# bontor_mbed_lowpan_rev_e.net
KiCad netlist of a schematic drawn in EAGLE
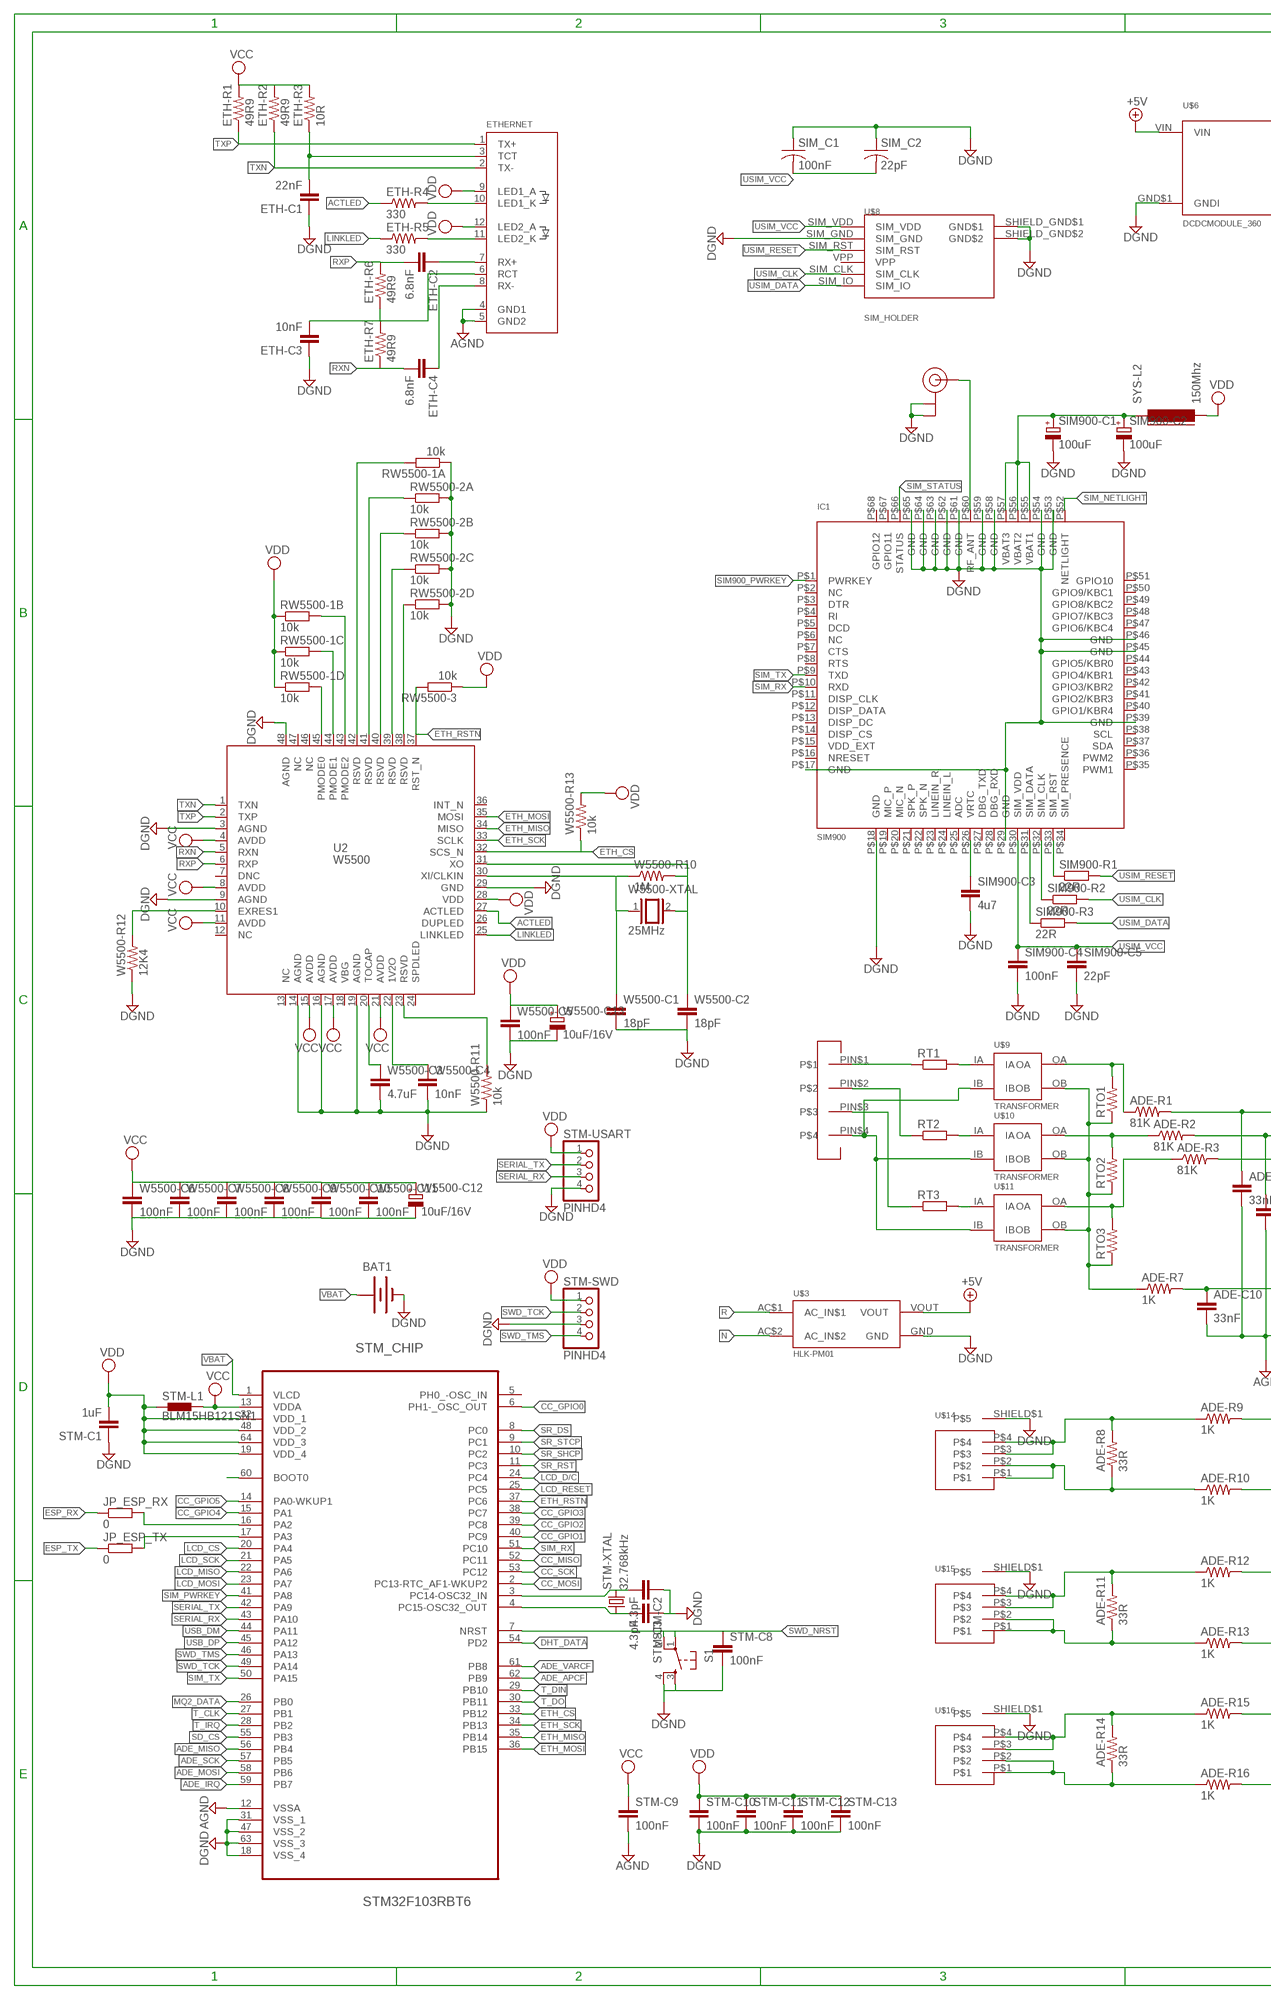
[diagram p0: schematic, sheet 1, part 1 of 2]
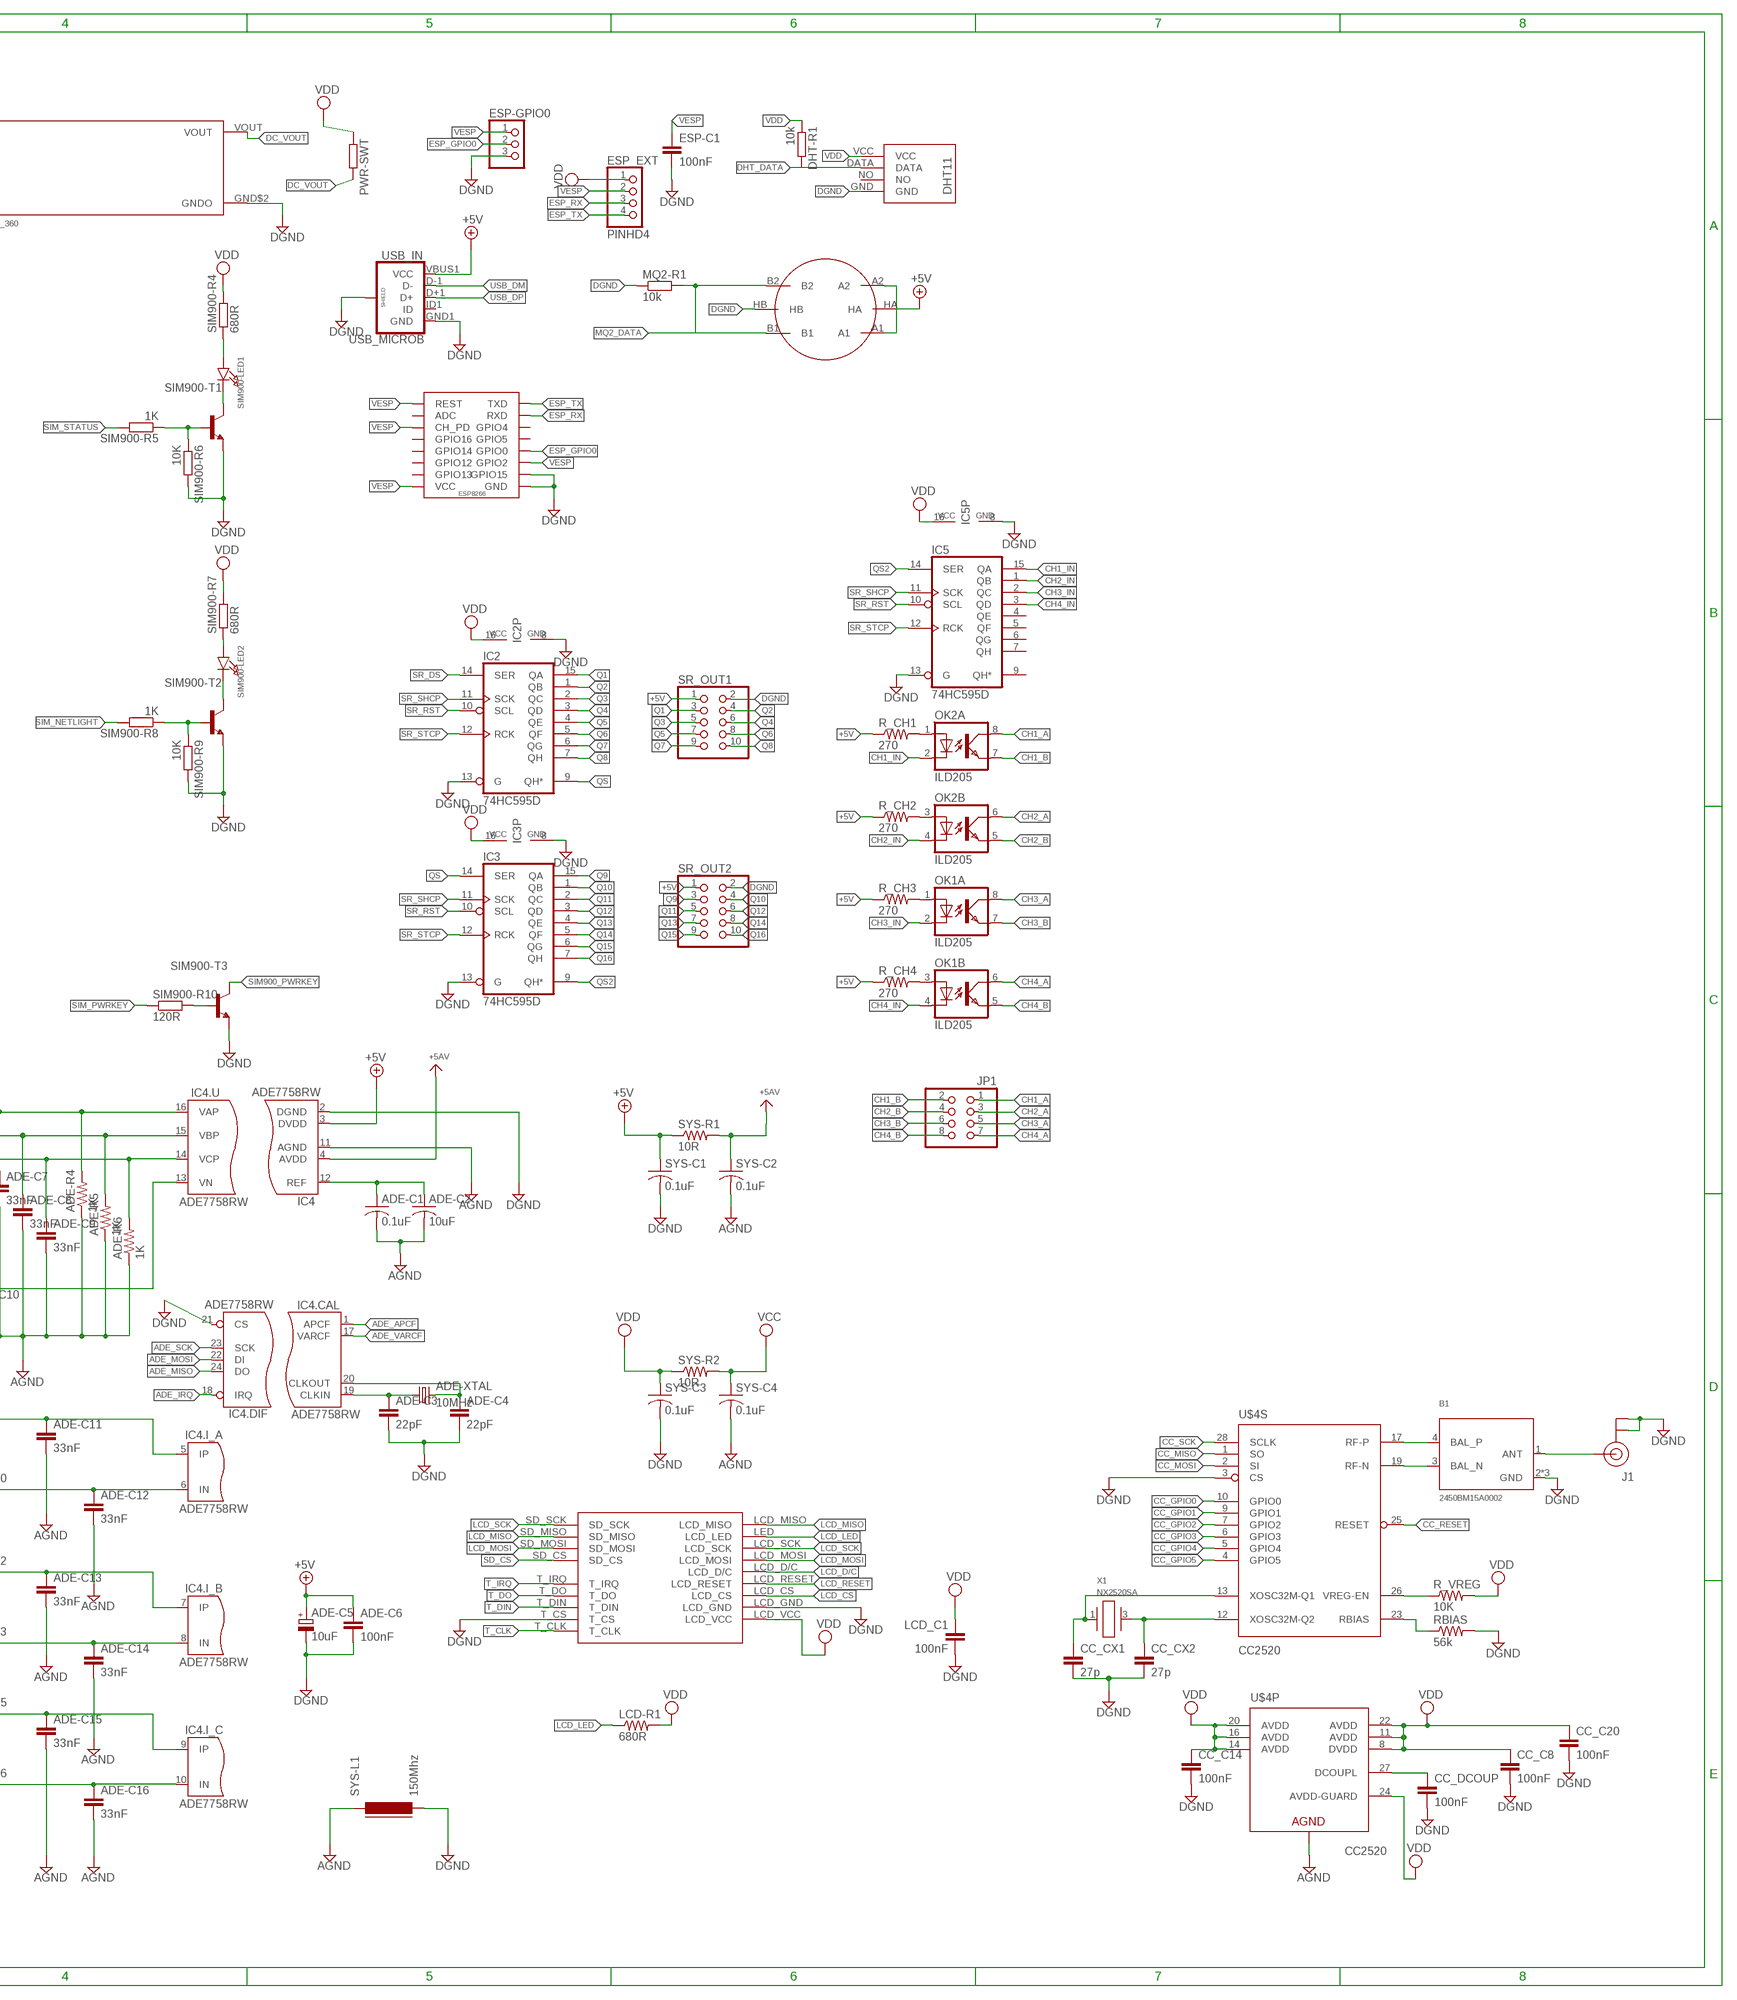
[diagram p1: schematic, sheet 1, part 2 of 2]

(export (version "E")
  (design (tool "Eeschema 10.0.6"))
  (components
    (comp (ref "ADE-C1")
      (value "0.1uF")
      (footprint "eagle-import:C0603@1")
      (libsource (lib "eagle-import") (part "C-USC0603"))
    )
    (comp (ref "ADE-C2")
      (value "10uF")
      (footprint "eagle-import:C0805K")
      (libsource (lib "eagle-import") (part "C-USC0805K"))
    )
    (comp (ref "ADE-C3")
      (value "22pF")
      (footprint "eagle-import:C0603")
      (libsource (lib "eagle-import") (part "C-EUC0603"))
    )
    (comp (ref "ADE-C4")
      (value "22pF")
      (footprint "eagle-import:C0603")
      (libsource (lib "eagle-import") (part "C-EUC0603"))
    )
    (comp (ref "ADE-C5")
      (value "10uF")
      (footprint "eagle-import:153CLV-0605")
      (libsource (lib "eagle-import") (part "CPOL-EU153CLV-0605"))
    )
    (comp (ref "ADE-C6")
      (value "100nF")
      (footprint "eagle-import:C0603")
      (libsource (lib "eagle-import") (part "C-EUC0603"))
    )
    (comp (ref "ADE-C7")
      (value "33nF")
      (footprint "eagle-import:0603-CAP")
      (libsource (lib "eagle-import") (part "CAP0603-CAP"))
    )
    (comp (ref "ADE-C8")
      (value "33nF")
      (footprint "eagle-import:0603-CAP")
      (libsource (lib "eagle-import") (part "CAP0603-CAP"))
    )
    (comp (ref "ADE-C9")
      (value "33nF")
      (footprint "eagle-import:0603-CAP")
      (libsource (lib "eagle-import") (part "CAP0603-CAP"))
    )
    (comp (ref "ADE-C10")
      (value "33nF")
      (footprint "eagle-import:0603-CAP")
      (libsource (lib "eagle-import") (part "CAP0603-CAP"))
    )
    (comp (ref "ADE-C11")
      (value "33nF")
      (footprint "eagle-import:0402-CAP")
      (libsource (lib "eagle-import") (part "CAP0402-CAP"))
    )
    (comp (ref "ADE-C12")
      (value "33nF")
      (footprint "eagle-import:0402-CAP")
      (libsource (lib "eagle-import") (part "CAP0402-CAP"))
    )
    (comp (ref "ADE-C13")
      (value "33nF")
      (footprint "eagle-import:0402-CAP")
      (libsource (lib "eagle-import") (part "CAP0402-CAP"))
    )
    (comp (ref "ADE-C14")
      (value "33nF")
      (footprint "eagle-import:0402-CAP")
      (libsource (lib "eagle-import") (part "CAP0402-CAP"))
    )
    (comp (ref "ADE-C15")
      (value "33nF")
      (footprint "eagle-import:0402-CAP")
      (libsource (lib "eagle-import") (part "CAP0402-CAP"))
    )
    (comp (ref "ADE-C16")
      (value "33nF")
      (footprint "eagle-import:0402-CAP")
      (libsource (lib "eagle-import") (part "CAP0402-CAP"))
    )
    (comp (ref "ADE-R1")
      (value "81K")
      (footprint "eagle-import:0603-RES")
      (libsource (lib "eagle-import") (part "RESISTOR0603-RES"))
    )
    (comp (ref "ADE-R2")
      (value "81K")
      (footprint "eagle-import:0603-RES")
      (libsource (lib "eagle-import") (part "RESISTOR0603-RES"))
    )
    (comp (ref "ADE-R3")
      (value "81K")
      (footprint "eagle-import:0603-RES")
      (libsource (lib "eagle-import") (part "RESISTOR0603-RES"))
    )
    (comp (ref "ADE-R4")
      (value "1K")
      (footprint "eagle-import:0603-RES")
      (libsource (lib "eagle-import") (part "RESISTOR0603-RES"))
    )
    (comp (ref "ADE-R5")
      (value "1K")
      (footprint "eagle-import:0603-RES")
      (libsource (lib "eagle-import") (part "RESISTOR0603-RES"))
    )
    (comp (ref "ADE-R6")
      (value "1K")
      (footprint "eagle-import:0603-RES")
      (libsource (lib "eagle-import") (part "RESISTOR0603-RES"))
    )
    (comp (ref "ADE-R7")
      (value "1K")
      (footprint "eagle-import:0603-RES")
      (libsource (lib "eagle-import") (part "RESISTOR0603-RES"))
    )
    (comp (ref "ADE-R8")
      (value "33R")
      (footprint "eagle-import:0402-RES")
      (libsource (lib "eagle-import") (part "RESISTOR0402-RES"))
    )
    (comp (ref "ADE-R9")
      (value "1K")
      (footprint "eagle-import:0402-RES")
      (libsource (lib "eagle-import") (part "RESISTOR0402-RES"))
    )
    (comp (ref "ADE-R10")
      (value "1K")
      (footprint "eagle-import:0402-RES")
      (libsource (lib "eagle-import") (part "RESISTOR0402-RES"))
    )
    (comp (ref "ADE-R11")
      (value "33R")
      (footprint "eagle-import:0402-RES")
      (libsource (lib "eagle-import") (part "RESISTOR0402-RES"))
    )
    (comp (ref "ADE-R12")
      (value "1K")
      (footprint "eagle-import:0402-RES")
      (libsource (lib "eagle-import") (part "RESISTOR0402-RES"))
    )
    (comp (ref "ADE-R13")
      (value "1K")
      (footprint "eagle-import:0402-RES")
      (libsource (lib "eagle-import") (part "RESISTOR0402-RES"))
    )
    (comp (ref "ADE-R14")
      (value "33R")
      (footprint "eagle-import:0402-RES")
      (libsource (lib "eagle-import") (part "RESISTOR0402-RES"))
    )
    (comp (ref "ADE-R15")
      (value "1K")
      (footprint "eagle-import:0402-RES")
      (libsource (lib "eagle-import") (part "RESISTOR0402-RES"))
    )
    (comp (ref "ADE-R16")
      (value "1K")
      (footprint "eagle-import:0402-RES")
      (libsource (lib "eagle-import") (part "RESISTOR0402-RES"))
    )
    (comp (ref "ADE-XTAL")
      (value "10MHz")
      (footprint "eagle-import:HC49US")
      (libsource (lib "eagle-import") (part "CRYSTALHC49US"))
    )
    (comp (ref "B1")
      (value "2450BM15A0002")
      (footprint "eagle-import:2450BM")
      (libsource (lib "eagle-import") (part "2450BM15A0002"))
    )
    (comp (ref "BAT1")
      (value "BATTERY12MM")
      (footprint "eagle-import:BATTCON_12MM")
      (libsource (lib "eagle-import") (part "BATTERY12MM"))
    )
    (comp (ref "CC_C8")
      (value "100nF")
      (footprint "eagle-import:C0402")
      (libsource (lib "eagle-import") (part "C-EUC0402"))
    )
    (comp (ref "CC_C14")
      (value "100nF")
      (footprint "eagle-import:C0402")
      (libsource (lib "eagle-import") (part "C-EUC0402"))
    )
    (comp (ref "CC_C20")
      (value "100nF")
      (footprint "eagle-import:C0402")
      (libsource (lib "eagle-import") (part "C-EUC0402"))
    )
    (comp (ref "CC_CX1")
      (value "27p")
      (footprint "eagle-import:C0201")
      (libsource (lib "eagle-import") (part "C-EUC0201"))
    )
    (comp (ref "CC_CX2")
      (value "27p")
      (footprint "eagle-import:C0201")
      (libsource (lib "eagle-import") (part "C-EUC0201"))
    )
    (comp (ref "CC_DCOUP")
      (value "100nF")
      (footprint "eagle-import:C0402")
      (libsource (lib "eagle-import") (part "C-EUC0402"))
    )
    (comp (ref "DHT-R1")
      (value "10k")
      (footprint "eagle-import:R0603")
      (libsource (lib "eagle-import") (part "resistor_R-EU_R0603"))
    )
    (comp (ref "ESP-C1")
      (value "100nF")
      (footprint "eagle-import:C0603")
      (libsource (lib "eagle-import") (part "C-EUC0603"))
    )
    (comp (ref "ESP-GPIO0")
      (value "PINHD-1X3")
      (footprint "eagle-import:1X03")
      (libsource (lib "eagle-import") (part "PINHD-1X3"))
    )
    (comp (ref "ESP_EXT")
      (value "PINHD4")
      (footprint "eagle-import:PINHD4")
      (libsource (lib "eagle-import") (part "PINHD4"))
    )
    (comp (ref "ETH-C1")
      (value "22nF")
      (footprint "eagle-import:C0603")
      (libsource (lib "eagle-import") (part "C-EUC0603"))
    )
    (comp (ref "ETH-C2")
      (value "6.8nF")
      (footprint "eagle-import:C0603")
      (libsource (lib "eagle-import") (part "C-EUC0603"))
    )
    (comp (ref "ETH-C3")
      (value "10nF")
      (footprint "eagle-import:C0603")
      (libsource (lib "eagle-import") (part "C-EUC0603"))
    )
    (comp (ref "ETH-C4")
      (value "6.8nF")
      (footprint "eagle-import:C0603")
      (libsource (lib "eagle-import") (part "C-EUC0603"))
    )
    (comp (ref "ETH-R1")
      (value "49R9")
      (footprint "eagle-import:R0603")
      (libsource (lib "eagle-import") (part "resistor_R-US_R0603"))
    )
    (comp (ref "ETH-R2")
      (value "49R9")
      (footprint "eagle-import:R0603")
      (libsource (lib "eagle-import") (part "resistor_R-US_R0603"))
    )
    (comp (ref "ETH-R3")
      (value "10R")
      (footprint "eagle-import:R0603")
      (libsource (lib "eagle-import") (part "resistor_R-US_R0603"))
    )
    (comp (ref "ETH-R4")
      (value "330")
      (footprint "eagle-import:R0603")
      (libsource (lib "eagle-import") (part "resistor_R-US_R0603"))
    )
    (comp (ref "ETH-R5")
      (value "330")
      (footprint "eagle-import:R0603")
      (libsource (lib "eagle-import") (part "resistor_R-US_R0603"))
    )
    (comp (ref "ETH-R6")
      (value "49R9")
      (footprint "eagle-import:R0603")
      (libsource (lib "eagle-import") (part "resistor_R-US_R0603"))
    )
    (comp (ref "ETH-R7")
      (value "49R9")
      (footprint "eagle-import:R0603")
      (libsource (lib "eagle-import") (part "resistor_R-US_R0603"))
    )
    (comp (ref "ETHERNET")
      (value "RJ45J0026D21BNL")
      (footprint "eagle-import:RJ45_PULSEJACK")
      (libsource (lib "eagle-import") (part "RJ45J0026D21BNL"))
    )
    (comp (ref "IC1")
      (value "SIM900")
      (footprint "eagle-import:SIM900_SMT")
      (libsource (lib "eagle-import") (part "GSM_SIM900_LITERAL"))
    )
    (comp (ref "IC2")
      (value "74HC595D")
      (footprint "eagle-import:SO16")
      (libsource (lib "eagle-import") (part "74595DHC"))
    )
    (comp (ref "IC3")
      (value "74HC595D")
      (footprint "eagle-import:SO16")
      (libsource (lib "eagle-import") (part "74595DHC"))
    )
    (comp (ref "IC4")
      (value "ADE7758RW")
      (footprint "eagle-import:SOIC24")
      (libsource (lib "eagle-import") (part "ADE7758RW"))
    )
    (comp (ref "IC5")
      (value "74HC595D")
      (footprint "eagle-import:SO16")
      (libsource (lib "eagle-import") (part "74595DHC"))
    )
    (comp (ref "J1")
      (value "U.FL")
      (footprint "eagle-import:U.FL")
      (libsource (lib "eagle-import") (part "SparkFun-Connectors_U.FL"))
    )
    (comp (ref "JP1")
      (value "PINHD-2X4")
      (footprint "eagle-import:2X04")
      (libsource (lib "eagle-import") (part "PINHD-2X4"))
    )
    (comp (ref "JP_ESP_RX")
      (value "0")
      (footprint "eagle-import:R0201")
      (libsource (lib "eagle-import") (part "R-EU_R0201"))
    )
    (comp (ref "JP_ESP_TX")
      (value "0")
      (footprint "eagle-import:R0201")
      (libsource (lib "eagle-import") (part "R-EU_R0201"))
    )
    (comp (ref "LCD-R1")
      (value "680R")
      (footprint "eagle-import:0603-RES")
      (libsource (lib "eagle-import") (part "RESISTOR0603-RES"))
    )
    (comp (ref "LCD_C1")
      (value "100nF")
      (footprint "eagle-import:C0603")
      (libsource (lib "eagle-import") (part "C-EUC0603"))
    )
    (comp (ref "MQ2-R1")
      (value "10k")
      (footprint "eagle-import:R0603")
      (libsource (lib "eagle-import") (part "resistor_R-EU_R0603"))
    )
    (comp (ref "OK1")
      (value "ILD205")
      (footprint "eagle-import:SOIC08")
      (fields (field (name "MF") "VISHAY/TELEFUNKEN") (field (name "MPN") "ILD205T"))
      (libsource (lib "eagle-import") (part "ILD205"))
    )
    (comp (ref "OK2")
      (value "ILD205")
      (footprint "eagle-import:SOIC08")
      (fields (field (name "MF") "VISHAY/TELEFUNKEN") (field (name "MPN") "ILD205T"))
      (libsource (lib "eagle-import") (part "ILD205"))
    )
    (comp (ref "PWR-SWT")
      (value "R-EU_R0402")
      (footprint "eagle-import:R0402")
      (libsource (lib "eagle-import") (part "R-EU_R0402"))
    )
    (comp (ref "RBIAS")
      (value "56k")
      (footprint "eagle-import:0402-RES")
      (libsource (lib "eagle-import") (part "RESISTOR0402-RES"))
    )
    (comp (ref "RT1")
      (value "R-EU_0309/V")
      (footprint "eagle-import:0309V")
      (libsource (lib "eagle-import") (part "R-EU_0309/V"))
    )
    (comp (ref "RT2")
      (value "R-EU_0309/V")
      (footprint "eagle-import:0309V")
      (libsource (lib "eagle-import") (part "R-EU_0309/V"))
    )
    (comp (ref "RT3")
      (value "R-EU_0309/V")
      (footprint "eagle-import:0309V")
      (libsource (lib "eagle-import") (part "R-EU_0309/V"))
    )
    (comp (ref "RTO1")
      (value "R-US_0309_12")
      (footprint "eagle-import:0309_12")
      (libsource (lib "eagle-import") (part "R-US_0309_12"))
    )
    (comp (ref "RTO2")
      (value "R-US_0309_12")
      (footprint "eagle-import:0309_12")
      (libsource (lib "eagle-import") (part "R-US_0309_12"))
    )
    (comp (ref "RTO3")
      (value "R-US_0309_12")
      (footprint "eagle-import:0309_12")
      (libsource (lib "eagle-import") (part "R-US_0309_12"))
    )
    (comp (ref "RW5500-1")
      (value "10k")
      (footprint "eagle-import:RN8P-4R-CRA06S")
      (libsource (lib "eagle-import") (part "RESISTOR_ARRAY_4"))
    )
    (comp (ref "RW5500-2")
      (value "10k")
      (footprint "eagle-import:RN8P-4R-CRA06S")
      (libsource (lib "eagle-import") (part "RESISTOR_ARRAY_4"))
    )
    (comp (ref "RW5500-3")
      (value "10k")
      (footprint "eagle-import:R0603")
      (libsource (lib "eagle-import") (part "R-EU_R0603"))
    )
    (comp (ref "R_CH1")
      (value "270")
      (footprint "eagle-import:0603-RES")
      (libsource (lib "eagle-import") (part "RESISTOR0603-RES"))
    )
    (comp (ref "R_CH2")
      (value "270")
      (footprint "eagle-import:0603-RES")
      (libsource (lib "eagle-import") (part "RESISTOR0603-RES"))
    )
    (comp (ref "R_CH3")
      (value "270")
      (footprint "eagle-import:0603-RES")
      (libsource (lib "eagle-import") (part "RESISTOR0603-RES"))
    )
    (comp (ref "R_CH4")
      (value "270")
      (footprint "eagle-import:0603-RES")
      (libsource (lib "eagle-import") (part "RESISTOR0603-RES"))
    )
    (comp (ref "R_VREG")
      (value "10K")
      (footprint "eagle-import:0402-RES")
      (libsource (lib "eagle-import") (part "RESISTOR0402-RES"))
    )
    (comp (ref "S1")
      (value "TAC_SWITCHPTH")
      (footprint "eagle-import:TACTILE-PTH")
      (libsource (lib "eagle-import") (part "TAC_SWITCHPTH"))
    )
    (comp (ref "SENSOR-MQ2")
      (value "METHANE_SENSOR")
      (footprint "eagle-import:MQ-3")
      (libsource (lib "eagle-import") (part "METHANE_SENSOR"))
    )
    (comp (ref "SIM900-C1")
      (value "100uF")
      (footprint "eagle-import:153CLV-0605")
      (libsource (lib "eagle-import") (part "CPOL-EU153CLV-0605"))
    )
    (comp (ref "SIM900-C2")
      (value "100uF")
      (footprint "eagle-import:153CLV-0605")
      (libsource (lib "eagle-import") (part "CPOL-EU153CLV-0605"))
    )
    (comp (ref "SIM900-C3")
      (value "4u7")
      (footprint "eagle-import:C0603")
      (libsource (lib "eagle-import") (part "C-EUC0603"))
    )
    (comp (ref "SIM900-C4")
      (value "100nF")
      (footprint "eagle-import:C0603")
      (libsource (lib "eagle-import") (part "C-EUC0603"))
    )
    (comp (ref "SIM900-C5")
      (value "22pF")
      (footprint "eagle-import:C0603")
      (libsource (lib "eagle-import") (part "C-EUC0603"))
    )
    (comp (ref "SIM900-LED1")
      (value "LED0805_NOOUTLINE")
      (footprint "eagle-import:CHIPLED_0805_NOOUTLINE")
      (libsource (lib "eagle-import") (part "LED0805_NOOUTLINE"))
    )
    (comp (ref "SIM900-LED2")
      (value "LED0805_NOOUTLINE")
      (footprint "eagle-import:CHIPLED_0805_NOOUTLINE")
      (libsource (lib "eagle-import") (part "LED0805_NOOUTLINE"))
    )
    (comp (ref "SIM900-R1")
      (value "22R")
      (footprint "eagle-import:R0603")
      (libsource (lib "eagle-import") (part "R-EU_R0603"))
    )
    (comp (ref "SIM900-R2")
      (value "22R")
      (footprint "eagle-import:R0603")
      (libsource (lib "eagle-import") (part "R-EU_R0603"))
    )
    (comp (ref "SIM900-R3")
      (value "22R")
      (footprint "eagle-import:R0603")
      (libsource (lib "eagle-import") (part "R-EU_R0603"))
    )
    (comp (ref "SIM900-R4")
      (value "680R")
      (footprint "eagle-import:R0402")
      (libsource (lib "eagle-import") (part "R-EU_R0402"))
    )
    (comp (ref "SIM900-R5")
      (value "1K")
      (footprint "eagle-import:R0603")
      (libsource (lib "eagle-import") (part "R-EU_R0603"))
    )
    (comp (ref "SIM900-R6")
      (value "10K")
      (footprint "eagle-import:R0603")
      (libsource (lib "eagle-import") (part "R-EU_R0603"))
    )
    (comp (ref "SIM900-R7")
      (value "680R")
      (footprint "eagle-import:R0603")
      (libsource (lib "eagle-import") (part "R-EU_R0603"))
    )
    (comp (ref "SIM900-R8")
      (value "1K")
      (footprint "eagle-import:R0603")
      (libsource (lib "eagle-import") (part "R-EU_R0603"))
    )
    (comp (ref "SIM900-R9")
      (value "10K")
      (footprint "eagle-import:R0603")
      (libsource (lib "eagle-import") (part "R-EU_R0603"))
    )
    (comp (ref "SIM900-R10")
      (value "120R")
      (footprint "eagle-import:R0603")
      (libsource (lib "eagle-import") (part "resistor_R-EU_R0603"))
    )
    (comp (ref "SIM900-T1")
      (value "MMBT2222ALT1-NPN-SOT23-BEC")
      (footprint "eagle-import:SOT23-BEC")
      (libsource (lib "eagle-import") (part "-NPN-SOT23-BECMMBT2222ALT1"))
    )
    (comp (ref "SIM900-T2")
      (value "MMBT2222ALT1-NPN-SOT23-BEC")
      (footprint "eagle-import:SOT23-BEC")
      (libsource (lib "eagle-import") (part "-NPN-SOT23-BECMMBT2222ALT1"))
    )
    (comp (ref "SIM900-T3")
      (value "MMBT2222ALT1-NPN-SOT23-BEC")
      (footprint "eagle-import:SOT23-BEC")
      (libsource (lib "eagle-import") (part "transistor-neu-to92_-NPN-SOT23-BECMMBT2222ALT1"))
    )
    (comp (ref "SIM_C1")
      (value "100nF")
      (footprint "eagle-import:C0603K")
      (libsource (lib "eagle-import") (part "C-USC0603K"))
    )
    (comp (ref "SIM_C2")
      (value "22pF")
      (footprint "eagle-import:C0603K")
      (libsource (lib "eagle-import") (part "C-USC0603K"))
    )
    (comp (ref "SR_OUT1")
      (value "PINHD-2X5")
      (footprint "eagle-import:2X05")
      (libsource (lib "eagle-import") (part "PINHD-2X5"))
    )
    (comp (ref "SR_OUT2")
      (value "PINHD-2X5")
      (footprint "eagle-import:2X05")
      (libsource (lib "eagle-import") (part "PINHD-2X5"))
    )
    (comp (ref "STM-C1")
      (value "1uF")
      (footprint "eagle-import:C0603")
      (libsource (lib "eagle-import") (part "C-EUC0603"))
    )
    (comp (ref "STM-C2")
      (value "4.3pF")
      (footprint "eagle-import:C0603")
      (libsource (lib "eagle-import") (part "C-EUC0603"))
    )
    (comp (ref "STM-C3")
      (value "4.3pF")
      (footprint "eagle-import:C0603")
      (libsource (lib "eagle-import") (part "C-EUC0603"))
    )
    (comp (ref "STM-C8")
      (value "100nF")
      (footprint "eagle-import:C0603")
      (libsource (lib "eagle-import") (part "C-EUC0603"))
    )
    (comp (ref "STM-C9")
      (value "100nF")
      (footprint "eagle-import:C0603")
      (libsource (lib "eagle-import") (part "C-EUC0603"))
    )
    (comp (ref "STM-C10")
      (value "100nF")
      (footprint "eagle-import:C0603")
      (libsource (lib "eagle-import") (part "C-EUC0603"))
    )
    (comp (ref "STM-C11")
      (value "100nF")
      (footprint "eagle-import:C0603")
      (libsource (lib "eagle-import") (part "C-EUC0603"))
    )
    (comp (ref "STM-C12")
      (value "100nF")
      (footprint "eagle-import:C0603")
      (libsource (lib "eagle-import") (part "C-EUC0603"))
    )
    (comp (ref "STM-C13")
      (value "100nF")
      (footprint "eagle-import:C0603")
      (libsource (lib "eagle-import") (part "C-EUC0603"))
    )
    (comp (ref "STM-L1")
      (value "BLM15HB121SN1")
      (footprint "eagle-import:0402")
      (libsource (lib "eagle-import") (part "BLM15HB121SN1"))
    )
    (comp (ref "STM-SWD")
      (value "PINHD4")
      (footprint "eagle-import:PINHD4")
      (libsource (lib "eagle-import") (part "PINHD4"))
    )
    (comp (ref "STM-USART")
      (value "PINHD4")
      (footprint "eagle-import:PINHD4")
      (libsource (lib "eagle-import") (part "PINHD4"))
    )
    (comp (ref "STM-XTAL")
      (value "32.768kHz")
      (footprint "eagle-import:TC26H")
      (libsource (lib "eagle-import") (part "CRYSTALTC26H"))
    )
    (comp (ref "STM_CHIP")
      (value "STM32F103RBT6")
      (footprint "eagle-import:QFP50P1200X1200X160-64N")
      (fields (field (name "MPN") "STM32L152RBT6"))
      (libsource (lib "eagle-import") (part "STM32L152RBT6"))
    )
    (comp (ref "SYS-C1")
      (value "0.1uF")
      (footprint "eagle-import:C0603@1")
      (libsource (lib "eagle-import") (part "C-USC0603"))
    )
    (comp (ref "SYS-C2")
      (value "0.1uF")
      (footprint "eagle-import:C0603@1")
      (libsource (lib "eagle-import") (part "C-USC0603"))
    )
    (comp (ref "SYS-C3")
      (value "0.1uF")
      (footprint "eagle-import:C0603@1")
      (libsource (lib "eagle-import") (part "C-USC0603"))
    )
    (comp (ref "SYS-C4")
      (value "0.1uF")
      (footprint "eagle-import:C0603@1")
      (libsource (lib "eagle-import") (part "C-USC0603"))
    )
    (comp (ref "SYS-L1")
      (value "150Mhz")
      (footprint "eagle-import:FB805")
      (libsource (lib "eagle-import") (part "FERRITE-0805"))
    )
    (comp (ref "SYS-L2")
      (value "150Mhz")
      (footprint "eagle-import:FB805")
      (libsource (lib "eagle-import") (part "FERRITE-0805"))
    )
    (comp (ref "SYS-R1")
      (value "10R")
      (footprint "eagle-import:0603-RES")
      (libsource (lib "eagle-import") (part "RESISTOR0603-RES"))
    )
    (comp (ref "SYS-R2")
      (value "10R")
      (footprint "eagle-import:0603-RES")
      (libsource (lib "eagle-import") (part "RESISTOR0603-RES"))
    )
    (comp (ref "U$3")
      (value "HLK-PM01")
      (footprint "eagle-import:HLK-PM01")
      (libsource (lib "eagle-import") (part "HLK-PM01"))
    )
    (comp (ref "U$4")
      (value "CC2520")
      (footprint "eagle-import:QFN50P500X500X100-29N")
      (libsource (lib "eagle-import") (part "CC2520"))
    )
    (comp (ref "U$5")
      (value "ESP8266WI12")
      (footprint "eagle-import:WI12")
      (libsource (lib "eagle-import") (part "ESP8266WI12"))
    )
    (comp (ref "U$6")
      (value "DCDCMODULE_360")
      (footprint "eagle-import:DCDCMODULE-360")
      (libsource (lib "eagle-import") (part "DCDCMODULE_360"))
    )
    (comp (ref "U$7")
      (value "U.FL")
      (footprint "eagle-import:U.FL")
      (libsource (lib "eagle-import") (part "U.FL"))
    )
    (comp (ref "U$8")
      (value "SIM_HOLDER")
      (footprint "eagle-import:SIMHOLDER-PUSHPUSH")
      (libsource (lib "eagle-import") (part "SIM_HOLDER"))
    )
    (comp (ref "U$9")
      (value "TRANSFORMER")
      (footprint "eagle-import:TV16")
      (libsource (lib "eagle-import") (part "TRANSFORMER"))
    )
    (comp (ref "U$10")
      (value "TRANSFORMER")
      (footprint "eagle-import:TV16")
      (libsource (lib "eagle-import") (part "TRANSFORMER"))
    )
    (comp (ref "U$11")
      (value "TRANSFORMER")
      (footprint "eagle-import:TV16")
      (libsource (lib "eagle-import") (part "TRANSFORMER"))
    )
    (comp (ref "U$12")
      (value "TERMINAL_BLOCK_TW")
      (footprint "eagle-import:TERMINAL-TWO-WAY")
      (libsource (lib "eagle-import") (part "TERMINAL_BLOCK_TW"))
    )
    (comp (ref "U$13")
      (value "LCD_2.4")
      (footprint "eagle-import:LCD_TOUCH_2-4")
      (libsource (lib "eagle-import") (part "LCD_2.4"))
    )
    (comp (ref "U$14")
      (value "RJ11-4P-V")
      (footprint "eagle-import:RJ11-4P-V")
      (libsource (lib "eagle-import") (part "RJ11-4P-V"))
    )
    (comp (ref "U$15")
      (value "RJ11-4P-V")
      (footprint "eagle-import:RJ11-4P-V")
      (libsource (lib "eagle-import") (part "RJ11-4P-V"))
    )
    (comp (ref "U$16")
      (value "RJ11-4P-V")
      (footprint "eagle-import:RJ11-4P-V")
      (libsource (lib "eagle-import") (part "RJ11-4P-V"))
    )
    (comp (ref "U$17")
      (value "DHT11")
      (footprint "eagle-import:DHT11")
      (libsource (lib "eagle-import") (part "DHT11"))
    )
    (comp (ref "U2")
      (value "W5500")
      (footprint "eagle-import:W5500")
      (libsource (lib "eagle-import") (part "W5500"))
    )
    (comp (ref "USB_IN")
      (value "USB_MICROB")
      (footprint "eagle-import:USB-B-MICRO-SMD_V03")
      (libsource (lib "eagle-import") (part "USB_MICROB_PLUGCONN-11752"))
    )
    (comp (ref "W5500-C1")
      (value "18pF")
      (footprint "eagle-import:C0603")
      (libsource (lib "eagle-import") (part "C-EUC0603"))
    )
    (comp (ref "W5500-C2")
      (value "18pF")
      (footprint "eagle-import:C0603")
      (libsource (lib "eagle-import") (part "C-EUC0603"))
    )
    (comp (ref "W5500-C3")
      (value "4.7uF")
      (footprint "eagle-import:C0603")
      (libsource (lib "eagle-import") (part "C-EUC0603"))
    )
    (comp (ref "W5500-C4")
      (value "10nF")
      (footprint "eagle-import:C0603")
      (libsource (lib "eagle-import") (part "C-EUC0603"))
    )
    (comp (ref "W5500-C5")
      (value "100nF")
      (footprint "eagle-import:C0603")
      (libsource (lib "eagle-import") (part "C-EUC0603"))
    )
    (comp (ref "W5500-C6")
      (value "100nF")
      (footprint "eagle-import:C0603")
      (libsource (lib "eagle-import") (part "C-EUC0603"))
    )
    (comp (ref "W5500-C7")
      (value "100nF")
      (footprint "eagle-import:C0603")
      (libsource (lib "eagle-import") (part "C-EUC0603"))
    )
    (comp (ref "W5500-C8")
      (value "100nF")
      (footprint "eagle-import:C0603")
      (libsource (lib "eagle-import") (part "C-EUC0603"))
    )
    (comp (ref "W5500-C9")
      (value "100nF")
      (footprint "eagle-import:C0603")
      (libsource (lib "eagle-import") (part "C-EUC0603"))
    )
    (comp (ref "W5500-C10")
      (value "100nF")
      (footprint "eagle-import:C0603")
      (libsource (lib "eagle-import") (part "C-EUC0603"))
    )
    (comp (ref "W5500-C11")
      (value "100nF")
      (footprint "eagle-import:C0603")
      (libsource (lib "eagle-import") (part "C-EUC0603"))
    )
    (comp (ref "W5500-C12")
      (value "10uF/16V")
      (footprint "eagle-import:153CLV-0605")
      (libsource (lib "eagle-import") (part "CPOL-EU153CLV-0605"))
    )
    (comp (ref "W5500-C13")
      (value "10uF/16V")
      (footprint "eagle-import:153CLV-0605")
      (libsource (lib "eagle-import") (part "CPOL-EU153CLV-0605"))
    )
    (comp (ref "W5500-R10")
      (value "1M")
      (footprint "eagle-import:R0603")
      (libsource (lib "eagle-import") (part "resistor_R-US_R0603"))
    )
    (comp (ref "W5500-R11")
      (value "10k")
      (footprint "eagle-import:R0603")
      (libsource (lib "eagle-import") (part "resistor_R-US_R0603"))
    )
    (comp (ref "W5500-R12")
      (value "12K4")
      (footprint "eagle-import:R0805")
      (libsource (lib "eagle-import") (part "resistor_R-US_R0805"))
    )
    (comp (ref "W5500-R13")
      (value "10k")
      (footprint "eagle-import:R0603")
      (libsource (lib "eagle-import") (part "resistor_R-US_R0603"))
    )
    (comp (ref "W5500-XTAL")
      (value "25MHz")
      (footprint "eagle-import:QS")
      (libsource (lib "eagle-import") (part "XTAL/S"))
    )
    (comp (ref "X1")
      (value "NX2520SA")
      (footprint "eagle-import:NX2520SA")
      (libsource (lib "eagle-import") (part "NX2520SA"))
    )
  )
  (nets
    (net (code "1") (name "+5AV") (class "Default")
      (node (ref "IC4") (pin "4") (pinfunction "AVDD_4") (pintype "power_in"))
      (node (ref "SYS-C2") (pin "1") (pinfunction "1_1") (pintype "passive"))
      (node (ref "SYS-R1") (pin "2") (pinfunction "2_2") (pintype "passive"))
    )
    (net (code "2") (name "+5V") (class "Default")
      (node (ref "ADE-C5") (pin "+") (pinfunction "+_+") (pintype "passive"))
      (node (ref "ADE-C6") (pin "1") (pinfunction "1_1") (pintype "passive"))
      (node (ref "IC4") (pin "3") (pinfunction "DVDD_3") (pintype "power_in"))
      (node (ref "R_CH1") (pin "1") (pinfunction "1_1") (pintype "passive"))
      (node (ref "R_CH2") (pin "1") (pinfunction "1_1") (pintype "passive"))
      (node (ref "R_CH3") (pin "1") (pinfunction "1_1") (pintype "passive"))
      (node (ref "R_CH4") (pin "1") (pinfunction "1_1") (pintype "passive"))
      (node (ref "SENSOR-MQ2") (pin "A1") (pinfunction "A1_A1") (pintype "bidirectional"))
      (node (ref "SENSOR-MQ2") (pin "A2") (pinfunction "A2_A2") (pintype "bidirectional"))
      (node (ref "SENSOR-MQ2") (pin "HA") (pinfunction "HA_HA") (pintype "bidirectional"))
      (node (ref "SR_OUT1") (pin "1") (pinfunction "1_1") (pintype "passive"))
      (node (ref "SR_OUT2") (pin "1") (pinfunction "1_1") (pintype "passive"))
      (node (ref "SYS-C1") (pin "1") (pinfunction "1_1") (pintype "passive"))
      (node (ref "SYS-R1") (pin "1") (pinfunction "1_1") (pintype "passive"))
      (node (ref "U$3") (pin "VOUT") (pinfunction "VOUT_VOUT") (pintype "bidirectional"))
      (node (ref "U$6") (pin "VIN") (pinfunction "VIN_VIN") (pintype "bidirectional"))
      (node (ref "USB_IN") (pin "VBUS1") (pinfunction "VCC_VBUS1") (pintype "bidirectional"))
    )
    (net (code "3") (name "/GPIO11") (class "Default")
      (node (ref "IC1") (pin "P$67") (pinfunction "GPIO11_P$67") (pintype "power_in"))
    )
    (net (code "4") (name "/GPIO12") (class "Default")
      (node (ref "IC1") (pin "P$68") (pinfunction "GPIO12_P$68") (pintype "power_in"))
    )
    (net (code "5") (name "ACTLED") (class "Default")
      (node (ref "ETH-R4") (pin "1") (pinfunction "1_1") (pintype "passive"))
      (node (ref "U2") (pin "27") (pinfunction "ACTLED_27") (pintype "passive"))
    )
    (net (code "6") (name "ADE_APCF") (class "Default")
      (node (ref "IC4") (pin "1") (pinfunction "APCF_1") (pintype "output"))
      (node (ref "STM_CHIP") (pin "62") (pinfunction "PB9_62") (pintype "bidirectional"))
    )
    (net (code "7") (name "ADE_IRQ") (class "Default")
      (node (ref "IC4") (pin "18") (pinfunction "IRQ_18") (pintype "output"))
      (node (ref "STM_CHIP") (pin "59") (pinfunction "PB7_59") (pintype "bidirectional"))
    )
    (net (code "8") (name "ADE_MISO") (class "Default")
      (node (ref "IC4") (pin "24") (pinfunction "DO_24") (pintype "output"))
      (node (ref "STM_CHIP") (pin "56") (pinfunction "PB4_56") (pintype "bidirectional"))
    )
    (net (code "9") (name "ADE_MOSI") (class "Default")
      (node (ref "IC4") (pin "22") (pinfunction "DI_22") (pintype "input"))
      (node (ref "STM_CHIP") (pin "58") (pinfunction "PB6_58") (pintype "bidirectional"))
    )
    (net (code "10") (name "ADE_SCK") (class "Default")
      (node (ref "IC4") (pin "23") (pinfunction "SCK_23") (pintype "input"))
      (node (ref "STM_CHIP") (pin "57") (pinfunction "PB5_57") (pintype "bidirectional"))
    )
    (net (code "11") (name "ADE_VARCF") (class "Default")
      (node (ref "IC4") (pin "17") (pinfunction "VARCF_17") (pintype "output"))
      (node (ref "STM_CHIP") (pin "61") (pinfunction "PB8_61") (pintype "bidirectional"))
    )
    (net (code "12") (name "AGND") (class "Default")
      (node (ref "ADE-C1") (pin "2") (pinfunction "2_2") (pintype "passive"))
      (node (ref "ADE-C10") (pin "2") (pinfunction "2_2") (pintype "passive"))
      (node (ref "ADE-C11") (pin "2") (pinfunction "2_2") (pintype "passive"))
      (node (ref "ADE-C12") (pin "2") (pinfunction "2_2") (pintype "passive"))
      (node (ref "ADE-C13") (pin "2") (pinfunction "2_2") (pintype "passive"))
      (node (ref "ADE-C14") (pin "2") (pinfunction "2_2") (pintype "passive"))
      (node (ref "ADE-C15") (pin "2") (pinfunction "2_2") (pintype "passive"))
      (node (ref "ADE-C16") (pin "2") (pinfunction "2_2") (pintype "passive"))
      (node (ref "ADE-C2") (pin "2") (pinfunction "2_2") (pintype "passive"))
      (node (ref "ADE-C7") (pin "2") (pinfunction "2_2") (pintype "passive"))
      (node (ref "ADE-C8") (pin "2") (pinfunction "2_2") (pintype "passive"))
      (node (ref "ADE-C9") (pin "2") (pinfunction "2_2") (pintype "passive"))
      (node (ref "ADE-R4") (pin "1") (pinfunction "1_1") (pintype "passive"))
      (node (ref "ADE-R5") (pin "1") (pinfunction "1_1") (pintype "passive"))
      (node (ref "ADE-R6") (pin "1") (pinfunction "1_1") (pintype "passive"))
      (node (ref "ETHERNET") (pin "4") (pinfunction "GND1_4") (pintype "bidirectional"))
      (node (ref "ETHERNET") (pin "5") (pinfunction "GND2_5") (pintype "bidirectional"))
      (node (ref "IC4") (pin "11") (pinfunction "AGND_11") (pintype "power_in"))
      (node (ref "STM-C9") (pin "2") (pinfunction "2_2") (pintype "passive"))
      (node (ref "STM_CHIP") (pin "12") (pinfunction "VSSA_12") (pintype "power_in"))
      (node (ref "SYS-C2") (pin "2") (pinfunction "2_2") (pintype "passive"))
      (node (ref "SYS-C4") (pin "2") (pinfunction "2_2") (pintype "passive"))
      (node (ref "SYS-L1") (pin "1") (pinfunction "1_1") (pintype "passive"))
      (node (ref "U$4") (pin "29") (pinfunction "AGND_29") (pintype "power_in"))
    )
    (net (code "13") (name "CC_GPIO0") (class "Default")
      (node (ref "STM_CHIP") (pin "6") (pinfunction "PH1-_OSC_OUT_6") (pintype "bidirectional"))
      (node (ref "U$4") (pin "10") (pinfunction "GPIO0_10") (pintype "output"))
    )
    (net (code "14") (name "CC_GPIO1") (class "Default")
      (node (ref "STM_CHIP") (pin "40") (pinfunction "PC9_40") (pintype "bidirectional"))
      (node (ref "U$4") (pin "9") (pinfunction "GPIO1_9") (pintype "output"))
    )
    (net (code "15") (name "CC_GPIO2") (class "Default")
      (node (ref "STM_CHIP") (pin "39") (pinfunction "PC8_39") (pintype "bidirectional"))
      (node (ref "U$4") (pin "7") (pinfunction "GPIO2_7") (pintype "bidirectional"))
    )
    (net (code "16") (name "CC_GPIO3") (class "Default")
      (node (ref "STM_CHIP") (pin "38") (pinfunction "PC7_38") (pintype "bidirectional"))
      (node (ref "U$4") (pin "6") (pinfunction "GPIO3_6") (pintype "bidirectional"))
    )
    (net (code "17") (name "CC_GPIO4") (class "Default")
      (node (ref "STM_CHIP") (pin "15") (pinfunction "PA1_15") (pintype "bidirectional"))
      (node (ref "U$4") (pin "5") (pinfunction "GPIO4_5") (pintype "bidirectional"))
    )
    (net (code "18") (name "CC_GPIO5") (class "Default")
      (node (ref "STM_CHIP") (pin "14") (pinfunction "PA0-WKUP1_14") (pintype "bidirectional"))
      (node (ref "U$4") (pin "4") (pinfunction "GPIO5_4") (pintype "bidirectional"))
    )
    (net (code "19") (name "CC_MISO") (class "Default")
      (node (ref "STM_CHIP") (pin "52") (pinfunction "PC11_52") (pintype "bidirectional"))
      (node (ref "U$4") (pin "1") (pinfunction "SO_1") (pintype "output"))
    )
    (net (code "20") (name "CC_MOSI") (class "Default")
      (node (ref "STM_CHIP") (pin "2") (pinfunction "PC13-RTC_AF1-WKUP2_2") (pintype "bidirectional"))
      (node (ref "U$4") (pin "2") (pinfunction "SI_2") (pintype "input"))
    )
    (net (code "21") (name "CC_RESET") (class "Default")
      (node (ref "U$4") (pin "25") (pinfunction "RESET_25") (pintype "input"))
    )
    (net (code "22") (name "CC_SCK") (class "Default")
      (node (ref "STM_CHIP") (pin "53") (pinfunction "PC12_53") (pintype "bidirectional"))
      (node (ref "U$4") (pin "28") (pinfunction "SCLK_28") (pintype "input"))
    )
    (net (code "23") (name "CH1_A") (class "Default")
      (node (ref "JP1") (pin "1") (pinfunction "1_1") (pintype "passive"))
      (node (ref "OK2") (pin "8") (pinfunction "COL_8") (pintype "passive"))
    )
    (net (code "24") (name "CH1_B") (class "Default")
      (node (ref "JP1") (pin "2") (pinfunction "2_2") (pintype "passive"))
      (node (ref "OK2") (pin "7") (pinfunction "EMIT_7") (pintype "passive"))
    )
    (net (code "25") (name "CH1_IN") (class "Default")
      (node (ref "IC5") (pin "15") (pinfunction "QA_15") (pintype "tri_state"))
      (node (ref "OK2") (pin "2") (pinfunction "C_2") (pintype "passive"))
    )
    (net (code "26") (name "CH2_A") (class "Default")
      (node (ref "JP1") (pin "3") (pinfunction "3_3") (pintype "passive"))
      (node (ref "OK2") (pin "6") (pinfunction "COL_6") (pintype "passive"))
    )
    (net (code "27") (name "CH2_B") (class "Default")
      (node (ref "JP1") (pin "4") (pinfunction "4_4") (pintype "passive"))
      (node (ref "OK2") (pin "5") (pinfunction "EMIT_5") (pintype "passive"))
    )
    (net (code "28") (name "CH2_IN") (class "Default")
      (node (ref "IC5") (pin "1") (pinfunction "QB_1") (pintype "tri_state"))
      (node (ref "OK2") (pin "4") (pinfunction "C_4") (pintype "passive"))
    )
    (net (code "29") (name "CH3_A") (class "Default")
      (node (ref "JP1") (pin "5") (pinfunction "5_5") (pintype "passive"))
      (node (ref "OK1") (pin "8") (pinfunction "COL_8") (pintype "passive"))
    )
    (net (code "30") (name "CH3_B") (class "Default")
      (node (ref "JP1") (pin "6") (pinfunction "6_6") (pintype "passive"))
      (node (ref "OK1") (pin "7") (pinfunction "EMIT_7") (pintype "passive"))
    )
    (net (code "31") (name "CH3_IN") (class "Default")
      (node (ref "IC5") (pin "2") (pinfunction "QC_2") (pintype "tri_state"))
      (node (ref "OK1") (pin "2") (pinfunction "C_2") (pintype "passive"))
    )
    (net (code "32") (name "CH4_A") (class "Default")
      (node (ref "JP1") (pin "7") (pinfunction "7_7") (pintype "passive"))
      (node (ref "OK1") (pin "6") (pinfunction "COL_6") (pintype "passive"))
    )
    (net (code "33") (name "CH4_B") (class "Default")
      (node (ref "JP1") (pin "8") (pinfunction "8_8") (pintype "passive"))
      (node (ref "OK1") (pin "5") (pinfunction "EMIT_5") (pintype "passive"))
    )
    (net (code "34") (name "CH4_IN") (class "Default")
      (node (ref "IC5") (pin "3") (pinfunction "QD_3") (pintype "tri_state"))
      (node (ref "OK1") (pin "4") (pinfunction "C_4") (pintype "passive"))
    )
    (net (code "35") (name "DC_VOUT") (class "Default")
      (node (ref "PWR-SWT") (pin "2") (pinfunction "2_2") (pintype "passive"))
      (node (ref "U$6") (pin "VOUT") (pinfunction "VOUT_VOUT") (pintype "bidirectional"))
    )
    (net (code "36") (name "DGND") (class "Default")
      (node (ref "ADE-C3") (pin "2") (pinfunction "2_2") (pintype "passive"))
      (node (ref "ADE-C4") (pin "2") (pinfunction "2_2") (pintype "passive"))
      (node (ref "ADE-C5") (pin "-") (pinfunction "-_-") (pintype "passive"))
      (node (ref "ADE-C6") (pin "2") (pinfunction "2_2") (pintype "passive"))
      (node (ref "B1") (pin "2") (pinfunction "GND_2") (pintype "bidirectional"))
      (node (ref "B1") (pin "5") (pinfunction "GND_5") (pintype "bidirectional"))
      (node (ref "B1") (pin "6") (pinfunction "GND_6") (pintype "bidirectional"))
      (node (ref "BAT1") (pin "GND") (pinfunction "-_GND") (pintype "power_in"))
      (node (ref "CC_C14") (pin "2") (pinfunction "2_2") (pintype "passive"))
      (node (ref "CC_C20") (pin "2") (pinfunction "2_2") (pintype "passive"))
      (node (ref "CC_C8") (pin "2") (pinfunction "2_2") (pintype "passive"))
      (node (ref "CC_CX1") (pin "2") (pinfunction "2_2") (pintype "passive"))
      (node (ref "CC_CX2") (pin "2") (pinfunction "2_2") (pintype "passive"))
      (node (ref "CC_DCOUP") (pin "2") (pinfunction "2_2") (pintype "passive"))
      (node (ref "ESP-C1") (pin "2") (pinfunction "2_2") (pintype "passive"))
      (node (ref "ESP-GPIO0") (pin "3") (pinfunction "3_3") (pintype "passive"))
      (node (ref "ETH-C1") (pin "1") (pinfunction "1_1") (pintype "passive"))
      (node (ref "ETH-C3") (pin "1") (pinfunction "1_1") (pintype "passive"))
      (node (ref "IC1") (pin "P$17") (pinfunction "GND_P$17") (pintype "power_in"))
      (node (ref "IC1") (pin "P$18") (pinfunction "GND_P$18") (pintype "power_in"))
      (node (ref "IC1") (pin "P$29") (pinfunction "GND_P$29") (pintype "power_in"))
      (node (ref "IC1") (pin "P$39") (pinfunction "GND_P$39") (pintype "power_in"))
      (node (ref "IC1") (pin "P$45") (pinfunction "GND_P$45") (pintype "power_in"))
      (node (ref "IC1") (pin "P$46") (pinfunction "GND_P$46") (pintype "power_in"))
      (node (ref "IC1") (pin "P$53") (pinfunction "GND_P$53") (pintype "power_in"))
      (node (ref "IC1") (pin "P$54") (pinfunction "GND_P$54") (pintype "power_in"))
      (node (ref "IC1") (pin "P$58") (pinfunction "GND_P$58") (pintype "power_in"))
      (node (ref "IC1") (pin "P$59") (pinfunction "GND_P$59") (pintype "power_in"))
      (node (ref "IC1") (pin "P$61") (pinfunction "GND_P$61") (pintype "power_in"))
      (node (ref "IC1") (pin "P$62") (pinfunction "GND_P$62") (pintype "power_in"))
      (node (ref "IC1") (pin "P$63") (pinfunction "GND_P$63") (pintype "power_in"))
      (node (ref "IC1") (pin "P$64") (pinfunction "GND_P$64") (pintype "power_in"))
      (node (ref "IC1") (pin "P$65") (pinfunction "GND_P$65") (pintype "power_in"))
      (node (ref "IC2") (pin "13") (pinfunction "G_13") (pintype "input"))
      (node (ref "IC2") (pin "8") (pinfunction "GND_8") (pintype "power_in"))
      (node (ref "IC3") (pin "13") (pinfunction "G_13") (pintype "input"))
      (node (ref "IC3") (pin "8") (pinfunction "GND_8") (pintype "power_in"))
      (node (ref "IC4") (pin "2") (pinfunction "DGND_2") (pintype "power_in"))
      (node (ref "IC4") (pin "21") (pinfunction "CS_21") (pintype "input"))
      (node (ref "IC5") (pin "13") (pinfunction "G_13") (pintype "input"))
      (node (ref "IC5") (pin "8") (pinfunction "GND_8") (pintype "power_in"))
      (node (ref "J1") (pin "P$1") (pinfunction "GND_P$1") (pintype "bidirectional"))
      (node (ref "J1") (pin "P$2") (pinfunction "GND_P$2") (pintype "bidirectional"))
      (node (ref "LCD_C1") (pin "2") (pinfunction "2_2") (pintype "passive"))
      (node (ref "MQ2-R1") (pin "1") (pinfunction "1_1") (pintype "passive"))
      (node (ref "RBIAS") (pin "2") (pinfunction "2_2") (pintype "passive"))
      (node (ref "RW5500-1") (pin "1") (pinfunction "1_1") (pintype "passive"))
      (node (ref "RW5500-2") (pin "5") (pinfunction "2_5") (pintype "passive"))
      (node (ref "RW5500-2") (pin "6") (pinfunction "2_6") (pintype "passive"))
      (node (ref "RW5500-2") (pin "7") (pinfunction "2_7") (pintype "passive"))
      (node (ref "RW5500-2") (pin "8") (pinfunction "2_8") (pintype "passive"))
      (node (ref "S1") (pin "3") (pinfunction "3_3") (pintype "passive"))
      (node (ref "S1") (pin "4") (pinfunction "4_4") (pintype "passive"))
      (node (ref "SENSOR-MQ2") (pin "HB") (pinfunction "HB_HB") (pintype "bidirectional"))
      (node (ref "SIM900-C1") (pin "-") (pinfunction "-_-") (pintype "passive"))
      (node (ref "SIM900-C2") (pin "-") (pinfunction "-_-") (pintype "passive"))
      (node (ref "SIM900-C3") (pin "2") (pinfunction "2_2") (pintype "passive"))
      (node (ref "SIM900-C4") (pin "2") (pinfunction "2_2") (pintype "passive"))
      (node (ref "SIM900-C5") (pin "2") (pinfunction "2_2") (pintype "passive"))
      (node (ref "SIM900-R6") (pin "2") (pinfunction "2_2") (pintype "passive"))
      (node (ref "SIM900-R9") (pin "2") (pinfunction "2_2") (pintype "passive"))
      (node (ref "SIM900-T1") (pin "E") (pinfunction "E_E") (pintype "passive"))
      (node (ref "SIM900-T2") (pin "E") (pinfunction "E_E") (pintype "passive"))
      (node (ref "SIM900-T3") (pin "E") (pinfunction "E_E") (pintype "passive"))
      (node (ref "SIM_C1") (pin "1") (pinfunction "1_1") (pintype "passive"))
      (node (ref "SIM_C2") (pin "1") (pinfunction "1_1") (pintype "passive"))
      (node (ref "SR_OUT1") (pin "2") (pinfunction "2_2") (pintype "passive"))
      (node (ref "SR_OUT2") (pin "2") (pinfunction "2_2") (pintype "passive"))
      (node (ref "STM-C1") (pin "1") (pinfunction "1_1") (pintype "passive"))
      (node (ref "STM-C10") (pin "2") (pinfunction "2_2") (pintype "passive"))
      (node (ref "STM-C11") (pin "2") (pinfunction "2_2") (pintype "passive"))
      (node (ref "STM-C12") (pin "2") (pinfunction "2_2") (pintype "passive"))
      (node (ref "STM-C13") (pin "2") (pinfunction "2_2") (pintype "passive"))
      (node (ref "STM-C2") (pin "1") (pinfunction "1_1") (pintype "passive"))
      (node (ref "STM-C3") (pin "1") (pinfunction "1_1") (pintype "passive"))
      (node (ref "STM-C8") (pin "2") (pinfunction "2_2") (pintype "passive"))
      (node (ref "STM-SWD") (pin "3") (pinfunction "3_3") (pintype "passive"))
      (node (ref "STM-USART") (pin "4") (pinfunction "4_4") (pintype "passive"))
      (node (ref "STM_CHIP") (pin "18") (pinfunction "VSS_4_18") (pintype "power_in"))
      (node (ref "STM_CHIP") (pin "31") (pinfunction "VSS_1_31") (pintype "power_in"))
      (node (ref "STM_CHIP") (pin "47") (pinfunction "VSS_2_47") (pintype "power_in"))
      (node (ref "STM_CHIP") (pin "63") (pinfunction "VSS_3_63") (pintype "power_in"))
      (node (ref "SYS-C1") (pin "2") (pinfunction "2_2") (pintype "passive"))
      (node (ref "SYS-C3") (pin "2") (pinfunction "2_2") (pintype "passive"))
      (node (ref "SYS-L1") (pin "2") (pinfunction "2_2") (pintype "passive"))
      (node (ref "U$13") (pin "LCD_GND") (pinfunction "LCD_GND_LCD_GND") (pintype "power_in"))
      (node (ref "U$13") (pin "T_CS") (pinfunction "T_CS_T_CS") (pintype "bidirectional"))
      (node (ref "U$14") (pin "SHIELD$1") (pinfunction "P$5_SHIELD$1") (pintype "bidirectional"))
      (node (ref "U$15") (pin "SHIELD$1") (pinfunction "P$5_SHIELD$1") (pintype "bidirectional"))
      (node (ref "U$16") (pin "SHIELD$1") (pinfunction "P$5_SHIELD$1") (pintype "bidirectional"))
      (node (ref "U$17") (pin "GND") (pinfunction "GND_GND") (pintype "bidirectional"))
      (node (ref "U$3") (pin "GND") (pinfunction "GND_GND") (pintype "bidirectional"))
      (node (ref "U$4") (pin "3") (pinfunction "CS_3") (pintype "input"))
      (node (ref "U$5") (pin "GND") (pinfunction "GND_GND") (pintype "bidirectional"))
      (node (ref "U$5") (pin "GPIO15") (pinfunction "GPIO15_GPIO15") (pintype "bidirectional"))
      (node (ref "U$6") (pin "GND$1") (pinfunction "GNDI_GND$1") (pintype "bidirectional"))
      (node (ref "U$6") (pin "GND$2") (pinfunction "GNDO_GND$2") (pintype "bidirectional"))
      (node (ref "U$7") (pin "P$1") (pinfunction "GND_P$1") (pintype "bidirectional"))
      (node (ref "U$7") (pin "P$2") (pinfunction "GND_P$2") (pintype "bidirectional"))
      (node (ref "U$8") (pin "SHIELD_GND$1") (pinfunction "GND$1_SHIELD_GND$1") (pintype "bidirectional"))
      (node (ref "U$8") (pin "SHIELD_GND$2") (pinfunction "GND$2_SHIELD_GND$2") (pintype "bidirectional"))
      (node (ref "U$8") (pin "SIM_GND") (pinfunction "SIM_GND_SIM_GND") (pintype "bidirectional"))
      (node (ref "U2") (pin "14") (pinfunction "AGND_14") (pintype "passive"))
      (node (ref "U2") (pin "16") (pinfunction "AGND_16") (pintype "passive"))
      (node (ref "U2") (pin "19") (pinfunction "AGND_19") (pintype "passive"))
      (node (ref "U2") (pin "29") (pinfunction "GND_29") (pintype "passive"))
      (node (ref "U2") (pin "3") (pinfunction "AGND_3") (pintype "passive"))
      (node (ref "U2") (pin "48") (pinfunction "AGND_48") (pintype "passive"))
      (node (ref "U2") (pin "9") (pinfunction "AGND_9") (pintype "passive"))
      (node (ref "USB_IN") (pin "GND1") (pinfunction "GND_GND1") (pintype "bidirectional"))
      (node (ref "USB_IN") (pin "SHIELD1") (pinfunction "SHIELD_SHIELD1") (pintype "bidirectional"))
      (node (ref "USB_IN") (pin "SHIELD2") (pinfunction "SHIELD_SHIELD2") (pintype "bidirectional"))
      (node (ref "USB_IN") (pin "SHIELD3") (pinfunction "SHIELD_SHIELD3") (pintype "bidirectional"))
      (node (ref "W5500-C1") (pin "2") (pinfunction "2_2") (pintype "passive"))
      (node (ref "W5500-C10") (pin "2") (pinfunction "2_2") (pintype "passive"))
      (node (ref "W5500-C11") (pin "2") (pinfunction "2_2") (pintype "passive"))
      (node (ref "W5500-C12") (pin "-") (pinfunction "-_-") (pintype "passive"))
      (node (ref "W5500-C13") (pin "-") (pinfunction "-_-") (pintype "passive"))
      (node (ref "W5500-C2") (pin "2") (pinfunction "2_2") (pintype "passive"))
      (node (ref "W5500-C3") (pin "2") (pinfunction "2_2") (pintype "passive"))
      (node (ref "W5500-C4") (pin "2") (pinfunction "2_2") (pintype "passive"))
      (node (ref "W5500-C5") (pin "2") (pinfunction "2_2") (pintype "passive"))
      (node (ref "W5500-C6") (pin "2") (pinfunction "2_2") (pintype "passive"))
      (node (ref "W5500-C7") (pin "2") (pinfunction "2_2") (pintype "passive"))
      (node (ref "W5500-C8") (pin "2") (pinfunction "2_2") (pintype "passive"))
      (node (ref "W5500-C9") (pin "2") (pinfunction "2_2") (pintype "passive"))
      (node (ref "W5500-R11") (pin "1") (pinfunction "1_1") (pintype "passive"))
      (node (ref "W5500-R12") (pin "1") (pinfunction "1_1") (pintype "passive"))
    )
    (net (code "37") (name "DHT_DATA") (class "Default")
      (node (ref "DHT-R1") (pin "2") (pinfunction "2_2") (pintype "passive"))
      (node (ref "STM_CHIP") (pin "54") (pinfunction "PD2_54") (pintype "bidirectional"))
      (node (ref "U$17") (pin "DATA") (pinfunction "DATA_DATA") (pintype "bidirectional"))
    )
    (net (code "38") (name "ESP_GPIO0") (class "Default")
      (node (ref "ESP-GPIO0") (pin "2") (pinfunction "2_2") (pintype "passive"))
      (node (ref "U$5") (pin "GPIO00") (pinfunction "GPIO0_GPIO00") (pintype "bidirectional"))
    )
    (net (code "39") (name "ESP_RX") (class "Default")
      (node (ref "ESP_EXT") (pin "3") (pinfunction "3_3") (pintype "passive"))
      (node (ref "JP_ESP_RX") (pin "1") (pinfunction "1_1") (pintype "passive"))
      (node (ref "U$5") (pin "RXD") (pinfunction "RXD_RXD") (pintype "bidirectional"))
    )
    (net (code "40") (name "ESP_TX") (class "Default")
      (node (ref "ESP_EXT") (pin "4") (pinfunction "4_4") (pintype "passive"))
      (node (ref "JP_ESP_TX") (pin "1") (pinfunction "1_1") (pintype "passive"))
      (node (ref "U$5") (pin "TXD") (pinfunction "TXD_TXD") (pintype "bidirectional"))
    )
    (net (code "41") (name "ETH_CS") (class "Default")
      (node (ref "STM_CHIP") (pin "33") (pinfunction "PB12_33") (pintype "bidirectional"))
      (node (ref "U2") (pin "32") (pinfunction "SCS_N_32") (pintype "passive"))
      (node (ref "W5500-R13") (pin "1") (pinfunction "1_1") (pintype "passive"))
    )
    (net (code "42") (name "ETH_MISO") (class "Default")
      (node (ref "STM_CHIP") (pin "35") (pinfunction "PB14_35") (pintype "bidirectional"))
      (node (ref "U2") (pin "34") (pinfunction "MISO_34") (pintype "passive"))
    )
    (net (code "43") (name "ETH_MOSI") (class "Default")
      (node (ref "STM_CHIP") (pin "36") (pinfunction "PB15_36") (pintype "bidirectional"))
      (node (ref "U2") (pin "35") (pinfunction "MOSI_35") (pintype "passive"))
    )
    (net (code "44") (name "ETH_RSTN") (class "Default")
      (node (ref "RW5500-3") (pin "2") (pinfunction "2_2") (pintype "passive"))
      (node (ref "STM_CHIP") (pin "37") (pinfunction "PC6_37") (pintype "bidirectional"))
      (node (ref "U2") (pin "37") (pinfunction "RST_N_37") (pintype "passive"))
    )
    (net (code "45") (name "ETH_SCK") (class "Default")
      (node (ref "STM_CHIP") (pin "34") (pinfunction "PB13_34") (pintype "bidirectional"))
      (node (ref "U2") (pin "33") (pinfunction "SCLK_33") (pintype "passive"))
    )
    (net (code "46") (name "LCD_CS") (class "Default")
      (node (ref "STM_CHIP") (pin "20") (pinfunction "PA4_20") (pintype "bidirectional"))
      (node (ref "U$13") (pin "LCD_CS") (pinfunction "LCD_CS_LCD_CS") (pintype "bidirectional"))
    )
    (net (code "47") (name "LCD_D{slash}C") (class "Default")
      (node (ref "STM_CHIP") (pin "24") (pinfunction "PC4_24") (pintype "bidirectional"))
      (node (ref "U$13") (pin "LCD_D/C") (pinfunction "LCD_D/C_LCD_D/C") (pintype "bidirectional"))
    )
    (net (code "48") (name "LCD_LED") (class "Default")
      (node (ref "LCD-R1") (pin "1") (pinfunction "1_1") (pintype "passive"))
      (node (ref "U$13") (pin "LED") (pinfunction "LCD_LED_LED") (pintype "bidirectional"))
    )
    (net (code "49") (name "LCD_MISO") (class "Default")
      (node (ref "STM_CHIP") (pin "22") (pinfunction "PA6_22") (pintype "bidirectional"))
      (node (ref "U$13") (pin "LCD_MISO") (pinfunction "LCD_MISO_LCD_MISO") (pintype "bidirectional"))
      (node (ref "U$13") (pin "SD_MISO") (pinfunction "SD_MISO_SD_MISO") (pintype "bidirectional"))
    )
    (net (code "50") (name "LCD_MOSI") (class "Default")
      (node (ref "STM_CHIP") (pin "23") (pinfunction "PA7_23") (pintype "bidirectional"))
      (node (ref "U$13") (pin "LCD_MOSI") (pinfunction "LCD_MOSI_LCD_MOSI") (pintype "bidirectional"))
      (node (ref "U$13") (pin "SD_MOSI") (pinfunction "SD_MOSI_SD_MOSI") (pintype "bidirectional"))
    )
    (net (code "51") (name "LCD_RESET") (class "Default")
      (node (ref "STM_CHIP") (pin "25") (pinfunction "PC5_25") (pintype "bidirectional"))
      (node (ref "U$13") (pin "LCD_RESET") (pinfunction "LCD_RESET_LCD_RESET") (pintype "bidirectional"))
    )
    (net (code "52") (name "LCD_SCK") (class "Default")
      (node (ref "STM_CHIP") (pin "21") (pinfunction "PA5_21") (pintype "bidirectional"))
      (node (ref "U$13") (pin "LCD_SCK") (pinfunction "LCD_SCK_LCD_SCK") (pintype "bidirectional"))
      (node (ref "U$13") (pin "SD_SCK") (pinfunction "SD_SCK_SD_SCK") (pintype "bidirectional"))
    )
    (net (code "53") (name "LINKLED") (class "Default")
      (node (ref "ETH-R5") (pin "1") (pinfunction "1_1") (pintype "passive"))
      (node (ref "U2") (pin "25") (pinfunction "LINKLED_25") (pintype "passive"))
    )
    (net (code "54") (name "MQ2_DATA") (class "Default")
      (node (ref "MQ2-R1") (pin "2") (pinfunction "2_2") (pintype "passive"))
      (node (ref "SENSOR-MQ2") (pin "B1") (pinfunction "B1_B1") (pintype "bidirectional"))
      (node (ref "SENSOR-MQ2") (pin "B2") (pinfunction "B2_B2") (pintype "bidirectional"))
      (node (ref "STM_CHIP") (pin "26") (pinfunction "PB0_26") (pintype "bidirectional"))
    )
    (net (code "55") (name "N") (class "Default")
      (node (ref "U$10") (pin "IB") (pinfunction "IB_IB") (pintype "bidirectional"))
      (node (ref "U$11") (pin "IB") (pinfunction "IB_IB") (pintype "bidirectional"))
      (node (ref "U$12") (pin "PIN$4") (pinfunction "P$4_PIN$4") (pintype "bidirectional"))
      (node (ref "U$3") (pin "AC$2") (pinfunction "AC_IN$2_AC$2") (pintype "bidirectional"))
      (node (ref "U$9") (pin "IB") (pinfunction "IB_IB") (pintype "bidirectional"))
    )
    (net (code "56") (name "Net-(ADE-R1-Pad1)") (class "Default")
      (node (ref "ADE-R1") (pin "1") (pinfunction "1_1") (pintype "passive"))
      (node (ref "RTO1") (pin "2") (pinfunction "2_2") (pintype "passive"))
      (node (ref "U$9") (pin "OA") (pinfunction "OA_OA") (pintype "bidirectional"))
    )
    (net (code "57") (name "Net-(ADE-R2-Pad1)") (class "Default")
      (node (ref "ADE-R2") (pin "1") (pinfunction "1_1") (pintype "passive"))
      (node (ref "RTO2") (pin "2") (pinfunction "2_2") (pintype "passive"))
      (node (ref "U$10") (pin "OA") (pinfunction "OA_OA") (pintype "bidirectional"))
    )
    (net (code "58") (name "Net-(ADE-R3-Pad1)") (class "Default")
      (node (ref "ADE-R3") (pin "1") (pinfunction "1_1") (pintype "passive"))
      (node (ref "RTO3") (pin "2") (pinfunction "2_2") (pintype "passive"))
      (node (ref "U$11") (pin "OA") (pinfunction "OA_OA") (pintype "bidirectional"))
    )
    (net (code "59") (name "Net-(ADE-R7-Pad1)") (class "Default")
      (node (ref "ADE-R7") (pin "1") (pinfunction "1_1") (pintype "passive"))
      (node (ref "RTO1") (pin "1") (pinfunction "1_1") (pintype "passive"))
      (node (ref "RTO2") (pin "1") (pinfunction "1_1") (pintype "passive"))
      (node (ref "RTO3") (pin "1") (pinfunction "1_1") (pintype "passive"))
      (node (ref "U$10") (pin "OB") (pinfunction "OB_OB") (pintype "bidirectional"))
      (node (ref "U$11") (pin "OB") (pinfunction "OB_OB") (pintype "bidirectional"))
      (node (ref "U$9") (pin "OB") (pinfunction "OB_OB") (pintype "bidirectional"))
    )
    (net (code "60") (name "Net-(ADE-R8-Pad2)") (class "Default")
      (node (ref "ADE-R8") (pin "2") (pinfunction "2_2") (pintype "passive"))
      (node (ref "ADE-R9") (pin "1") (pinfunction "1_1") (pintype "passive"))
      (node (ref "U$14") (pin "P$3") (pinfunction "P$3_P$3") (pintype "bidirectional"))
      (node (ref "U$14") (pin "P$4") (pinfunction "P$4_P$4") (pintype "bidirectional"))
    )
    (net (code "61") (name "Net-(ADE-R10-Pad1)") (class "Default")
      (node (ref "ADE-R10") (pin "1") (pinfunction "1_1") (pintype "passive"))
      (node (ref "ADE-R8") (pin "1") (pinfunction "1_1") (pintype "passive"))
      (node (ref "U$14") (pin "P$1") (pinfunction "P$1_P$1") (pintype "bidirectional"))
      (node (ref "U$14") (pin "P$2") (pinfunction "P$2_P$2") (pintype "bidirectional"))
    )
    (net (code "62") (name "Net-(ADE-R11-Pad1)") (class "Default")
      (node (ref "ADE-R11") (pin "1") (pinfunction "1_1") (pintype "passive"))
      (node (ref "ADE-R13") (pin "1") (pinfunction "1_1") (pintype "passive"))
      (node (ref "U$15") (pin "P$1") (pinfunction "P$1_P$1") (pintype "bidirectional"))
      (node (ref "U$15") (pin "P$2") (pinfunction "P$2_P$2") (pintype "bidirectional"))
    )
    (net (code "63") (name "Net-(ADE-R11-Pad2)") (class "Default")
      (node (ref "ADE-R11") (pin "2") (pinfunction "2_2") (pintype "passive"))
      (node (ref "ADE-R12") (pin "1") (pinfunction "1_1") (pintype "passive"))
      (node (ref "U$15") (pin "P$3") (pinfunction "P$3_P$3") (pintype "bidirectional"))
      (node (ref "U$15") (pin "P$4") (pinfunction "P$4_P$4") (pintype "bidirectional"))
    )
    (net (code "64") (name "Net-(ADE-R14-Pad1)") (class "Default")
      (node (ref "ADE-R14") (pin "1") (pinfunction "1_1") (pintype "passive"))
      (node (ref "ADE-R16") (pin "1") (pinfunction "1_1") (pintype "passive"))
      (node (ref "U$16") (pin "P$1") (pinfunction "P$1_P$1") (pintype "bidirectional"))
      (node (ref "U$16") (pin "P$2") (pinfunction "P$2_P$2") (pintype "bidirectional"))
    )
    (net (code "65") (name "Net-(ADE-R14-Pad2)") (class "Default")
      (node (ref "ADE-R14") (pin "2") (pinfunction "2_2") (pintype "passive"))
      (node (ref "ADE-R15") (pin "1") (pinfunction "1_1") (pintype "passive"))
      (node (ref "U$16") (pin "P$3") (pinfunction "P$3_P$3") (pintype "bidirectional"))
      (node (ref "U$16") (pin "P$4") (pinfunction "P$4_P$4") (pintype "bidirectional"))
    )
    (net (code "66") (name "Net-(B1-ANT)") (class "Default")
      (node (ref "B1") (pin "1") (pinfunction "ANT_1") (pintype "bidirectional"))
      (node (ref "J1") (pin "P$3") (pinfunction "SIGNAL_P$3") (pintype "bidirectional"))
    )
    (net (code "67") (name "Net-(B1-BAL_N)") (class "Default")
      (node (ref "B1") (pin "3") (pinfunction "BAL_N_3") (pintype "bidirectional"))
      (node (ref "U$4") (pin "19") (pinfunction "RF-N_19") (pintype "bidirectional"))
    )
    (net (code "68") (name "Net-(B1-BAL_P)") (class "Default")
      (node (ref "B1") (pin "4") (pinfunction "BAL_P_4") (pintype "bidirectional"))
      (node (ref "U$4") (pin "17") (pinfunction "RF-P_17") (pintype "bidirectional"))
    )
    (net (code "69") (name "Net-(ETHERNET-LED1_K)") (class "Default")
      (node (ref "ETH-R4") (pin "2") (pinfunction "2_2") (pintype "passive"))
      (node (ref "ETHERNET") (pin "10") (pinfunction "LED1_K_10") (pintype "bidirectional"))
    )
    (net (code "70") (name "Net-(ETHERNET-LED2_K)") (class "Default")
      (node (ref "ETH-R5") (pin "2") (pinfunction "2_2") (pintype "passive"))
      (node (ref "ETHERNET") (pin "11") (pinfunction "LED2_K_11") (pintype "bidirectional"))
    )
    (net (code "71") (name "Net-(ETHERNET-RCT)") (class "Default")
      (node (ref "ETH-C3") (pin "2") (pinfunction "2_2") (pintype "passive"))
      (node (ref "ETH-R6") (pin "1") (pinfunction "1_1") (pintype "passive"))
      (node (ref "ETH-R7") (pin "2") (pinfunction "2_2") (pintype "passive"))
      (node (ref "ETHERNET") (pin "6") (pinfunction "RCT_6") (pintype "bidirectional"))
    )
    (net (code "72") (name "Net-(ETHERNET-RX+)") (class "Default")
      (node (ref "ETH-C2") (pin "1") (pinfunction "1_1") (pintype "passive"))
      (node (ref "ETHERNET") (pin "7") (pinfunction "RX+_7") (pintype "bidirectional"))
    )
    (net (code "73") (name "Net-(ETHERNET-RX-)") (class "Default")
      (node (ref "ETH-C4") (pin "1") (pinfunction "1_1") (pintype "passive"))
      (node (ref "ETHERNET") (pin "8") (pinfunction "RX-_8") (pintype "bidirectional"))
    )
    (net (code "74") (name "Net-(ETHERNET-TCT)") (class "Default")
      (node (ref "ETH-C1") (pin "2") (pinfunction "2_2") (pintype "passive"))
      (node (ref "ETH-R3") (pin "1") (pinfunction "1_1") (pintype "passive"))
      (node (ref "ETHERNET") (pin "3") (pinfunction "TCT_3") (pintype "bidirectional"))
    )
    (net (code "75") (name "Net-(IC1-RF_ANT)") (class "Default")
      (node (ref "IC1") (pin "P$60") (pinfunction "RF_ANT_P$60") (pintype "bidirectional"))
      (node (ref "U$7") (pin "P$3") (pinfunction "SIGNAL_P$3") (pintype "bidirectional"))
    )
    (net (code "76") (name "Net-(IC1-SIM_CLK)") (class "Default")
      (node (ref "IC1") (pin "P$32") (pinfunction "SIM_CLK_P$32") (pintype "bidirectional"))
      (node (ref "SIM900-R2") (pin "1") (pinfunction "1_1") (pintype "passive"))
    )
    (net (code "77") (name "Net-(IC1-SIM_DATA)") (class "Default")
      (node (ref "IC1") (pin "P$31") (pinfunction "SIM_DATA_P$31") (pintype "bidirectional"))
      (node (ref "SIM900-R3") (pin "1") (pinfunction "1_1") (pintype "passive"))
    )
    (net (code "78") (name "Net-(IC1-SIM_RST)") (class "Default")
      (node (ref "IC1") (pin "P$33") (pinfunction "SIM_RST_P$33") (pintype "bidirectional"))
      (node (ref "SIM900-R1") (pin "1") (pinfunction "1_1") (pintype "passive"))
    )
    (net (code "79") (name "Net-(IC1-VBAT1)") (class "Default")
      (node (ref "IC1") (pin "P$55") (pinfunction "VBAT1_P$55") (pintype "power_in"))
      (node (ref "IC1") (pin "P$56") (pinfunction "VBAT2_P$56") (pintype "power_in"))
      (node (ref "IC1") (pin "P$57") (pinfunction "VBAT3_P$57") (pintype "power_in"))
      (node (ref "SIM900-C1") (pin "+") (pinfunction "+_+") (pintype "passive"))
      (node (ref "SIM900-C2") (pin "+") (pinfunction "+_+") (pintype "passive"))
      (node (ref "SYS-L2") (pin "1") (pinfunction "1_1") (pintype "passive"))
    )
    (net (code "80") (name "Net-(IC1-VRTC)") (class "Default")
      (node (ref "IC1") (pin "P$26") (pinfunction "VRTC_P$26") (pintype "power_in"))
      (node (ref "SIM900-C3") (pin "1") (pinfunction "1_1") (pintype "passive"))
    )
    (net (code "81") (name "Net-(IC4A-CLKIN)") (class "Default")
      (node (ref "ADE-C3") (pin "1") (pinfunction "1_1") (pintype "passive"))
      (node (ref "ADE-XTAL") (pin "1") (pinfunction "1_1") (pintype "passive"))
      (node (ref "IC4") (pin "19") (pinfunction "CLKIN_19") (pintype "input"))
    )
    (net (code "82") (name "Net-(IC4A-CLKOUT)") (class "Default")
      (node (ref "ADE-C4") (pin "1") (pinfunction "1_1") (pintype "passive"))
      (node (ref "ADE-XTAL") (pin "2") (pinfunction "2_2") (pintype "passive"))
      (node (ref "IC4") (pin "20") (pinfunction "CLKOUT_20") (pintype "output"))
    )
    (net (code "83") (name "Net-(IC4C-IN)") (class "Default")
      (node (ref "ADE-C12") (pin "1") (pinfunction "1_1") (pintype "passive"))
      (node (ref "ADE-R10") (pin "2") (pinfunction "2_2") (pintype "passive"))
      (node (ref "IC4") (pin "6") (pinfunction "IN_6") (pintype "input"))
    )
    (net (code "84") (name "Net-(IC4C-IP)") (class "Default")
      (node (ref "ADE-C11") (pin "1") (pinfunction "1_1") (pintype "passive"))
      (node (ref "ADE-R9") (pin "2") (pinfunction "2_2") (pintype "passive"))
      (node (ref "IC4") (pin "5") (pinfunction "IP_5") (pintype "input"))
    )
    (net (code "85") (name "Net-(IC4D-IN)") (class "Default")
      (node (ref "ADE-C14") (pin "1") (pinfunction "1_1") (pintype "passive"))
      (node (ref "ADE-R13") (pin "2") (pinfunction "2_2") (pintype "passive"))
      (node (ref "IC4") (pin "8") (pinfunction "IN_8") (pintype "input"))
    )
    (net (code "86") (name "Net-(IC4D-IP)") (class "Default")
      (node (ref "ADE-C13") (pin "1") (pinfunction "1_1") (pintype "passive"))
      (node (ref "ADE-R12") (pin "2") (pinfunction "2_2") (pintype "passive"))
      (node (ref "IC4") (pin "7") (pinfunction "IP_7") (pintype "input"))
    )
    (net (code "87") (name "Net-(IC4E-IN)") (class "Default")
      (node (ref "ADE-C16") (pin "1") (pinfunction "1_1") (pintype "passive"))
      (node (ref "ADE-R16") (pin "2") (pinfunction "2_2") (pintype "passive"))
      (node (ref "IC4") (pin "10") (pinfunction "IN_10") (pintype "input"))
    )
    (net (code "88") (name "Net-(IC4E-IP)") (class "Default")
      (node (ref "ADE-C15") (pin "1") (pinfunction "1_1") (pintype "passive"))
      (node (ref "ADE-R15") (pin "2") (pinfunction "2_2") (pintype "passive"))
      (node (ref "IC4") (pin "9") (pinfunction "IP_9") (pintype "input"))
    )
    (net (code "89") (name "Net-(IC4F-REF)") (class "Default")
      (node (ref "ADE-C1") (pin "1") (pinfunction "1_1") (pintype "passive"))
      (node (ref "ADE-C2") (pin "1") (pinfunction "1_1") (pintype "passive"))
      (node (ref "IC4") (pin "12") (pinfunction "REF_12") (pintype "bidirectional"))
    )
    (net (code "90") (name "Net-(IC4G-VAP)") (class "Default")
      (node (ref "ADE-C7") (pin "1") (pinfunction "1_1") (pintype "passive"))
      (node (ref "ADE-R1") (pin "2") (pinfunction "2_2") (pintype "passive"))
      (node (ref "ADE-R4") (pin "2") (pinfunction "2_2") (pintype "passive"))
      (node (ref "IC4") (pin "16") (pinfunction "VAP_16") (pintype "input"))
    )
    (net (code "91") (name "Net-(IC4G-VBP)") (class "Default")
      (node (ref "ADE-C8") (pin "1") (pinfunction "1_1") (pintype "passive"))
      (node (ref "ADE-R2") (pin "2") (pinfunction "2_2") (pintype "passive"))
      (node (ref "ADE-R5") (pin "2") (pinfunction "2_2") (pintype "passive"))
      (node (ref "IC4") (pin "15") (pinfunction "VBP_15") (pintype "input"))
    )
    (net (code "92") (name "Net-(IC4G-VCP)") (class "Default")
      (node (ref "ADE-C9") (pin "1") (pinfunction "1_1") (pintype "passive"))
      (node (ref "ADE-R3") (pin "2") (pinfunction "2_2") (pintype "passive"))
      (node (ref "ADE-R6") (pin "2") (pinfunction "2_2") (pintype "passive"))
      (node (ref "IC4") (pin "14") (pinfunction "VCP_14") (pintype "input"))
    )
    (net (code "93") (name "Net-(IC4G-VN)") (class "Default")
      (node (ref "ADE-C10") (pin "1") (pinfunction "1_1") (pintype "passive"))
      (node (ref "ADE-R7") (pin "2") (pinfunction "2_2") (pintype "passive"))
      (node (ref "IC4") (pin "13") (pinfunction "VN_13") (pintype "input"))
    )
    (net (code "94") (name "Net-(OK1A-A)") (class "Default")
      (node (ref "OK1") (pin "1") (pinfunction "A_1") (pintype "passive"))
      (node (ref "R_CH3") (pin "2") (pinfunction "2_2") (pintype "passive"))
    )
    (net (code "95") (name "Net-(OK1B-A)") (class "Default")
      (node (ref "OK1") (pin "3") (pinfunction "A_3") (pintype "passive"))
      (node (ref "R_CH4") (pin "2") (pinfunction "2_2") (pintype "passive"))
    )
    (net (code "96") (name "Net-(OK2A-A)") (class "Default")
      (node (ref "OK2") (pin "1") (pinfunction "A_1") (pintype "passive"))
      (node (ref "R_CH1") (pin "2") (pinfunction "2_2") (pintype "passive"))
    )
    (net (code "97") (name "Net-(OK2B-A)") (class "Default")
      (node (ref "OK2") (pin "3") (pinfunction "A_3") (pintype "passive"))
      (node (ref "R_CH2") (pin "2") (pinfunction "2_2") (pintype "passive"))
    )
    (net (code "98") (name "Net-(RT1-Pad2)") (class "Default")
      (node (ref "RT1") (pin "2") (pinfunction "2_2") (pintype "passive"))
      (node (ref "U$9") (pin "IA") (pinfunction "IA_IA") (pintype "bidirectional"))
    )
    (net (code "99") (name "Net-(RT2-Pad2)") (class "Default")
      (node (ref "RT2") (pin "2") (pinfunction "2_2") (pintype "passive"))
      (node (ref "U$10") (pin "IA") (pinfunction "IA_IA") (pintype "bidirectional"))
    )
    (net (code "100") (name "Net-(RT3-Pad2)") (class "Default")
      (node (ref "RT3") (pin "2") (pinfunction "2_2") (pintype "passive"))
      (node (ref "U$11") (pin "IA") (pinfunction "IA_IA") (pintype "bidirectional"))
    )
    (net (code "101") (name "Net-(RW5500-1A-2)") (class "Default")
      (node (ref "RW5500-1") (pin "8") (pinfunction "2_8") (pintype "passive"))
      (node (ref "U2") (pin "42") (pinfunction "RSVD_42") (pintype "passive"))
    )
    (net (code "102") (name "Net-(RW5500-1B-2)") (class "Default")
      (node (ref "RW5500-1") (pin "7") (pinfunction "2_7") (pintype "passive"))
      (node (ref "U2") (pin "43") (pinfunction "PMODE2_43") (pintype "passive"))
    )
    (net (code "103") (name "Net-(RW5500-1C-2)") (class "Default")
      (node (ref "RW5500-1") (pin "6") (pinfunction "2_6") (pintype "passive"))
      (node (ref "U2") (pin "44") (pinfunction "PMODE1_44") (pintype "passive"))
    )
    (net (code "104") (name "Net-(RW5500-1D-2)") (class "Default")
      (node (ref "RW5500-1") (pin "5") (pinfunction "2_5") (pintype "passive"))
      (node (ref "U2") (pin "45") (pinfunction "PMODE0_45") (pintype "passive"))
    )
    (net (code "105") (name "Net-(RW5500-2-Pad1)") (class "Default")
      (node (ref "RW5500-2") (pin "1") (pinfunction "1_1") (pintype "passive"))
      (node (ref "U2") (pin "41") (pinfunction "RSVD_41") (pintype "passive"))
    )
    (net (code "106") (name "Net-(RW5500-2B-1)") (class "Default")
      (node (ref "RW5500-2") (pin "2") (pinfunction "1_2") (pintype "passive"))
      (node (ref "U2") (pin "40") (pinfunction "RSVD_40") (pintype "passive"))
    )
    (net (code "107") (name "Net-(RW5500-2C-1)") (class "Default")
      (node (ref "RW5500-2") (pin "3") (pinfunction "1_3") (pintype "passive"))
      (node (ref "U2") (pin "39") (pinfunction "RSVD_39") (pintype "passive"))
    )
    (net (code "108") (name "Net-(RW5500-2D-1)") (class "Default")
      (node (ref "RW5500-2") (pin "4") (pinfunction "1_4") (pintype "passive"))
      (node (ref "U2") (pin "38") (pinfunction "RSVD_38") (pintype "passive"))
    )
    (net (code "109") (name "Net-(SIM900-LED1-PadA)") (class "Default")
      (node (ref "SIM900-LED1") (pin "A") (pinfunction "A_A") (pintype "passive"))
      (node (ref "SIM900-R4") (pin "1") (pinfunction "1_1") (pintype "passive"))
    )
    (net (code "110") (name "Net-(SIM900-LED1-PadC)") (class "Default")
      (node (ref "SIM900-LED1") (pin "C") (pinfunction "C_C") (pintype "passive"))
      (node (ref "SIM900-T1") (pin "C") (pinfunction "C_C") (pintype "passive"))
    )
    (net (code "111") (name "Net-(SIM900-LED2-PadA)") (class "Default")
      (node (ref "SIM900-LED2") (pin "A") (pinfunction "A_A") (pintype "passive"))
      (node (ref "SIM900-R7") (pin "1") (pinfunction "1_1") (pintype "passive"))
    )
    (net (code "112") (name "Net-(SIM900-LED2-PadC)") (class "Default")
      (node (ref "SIM900-LED2") (pin "C") (pinfunction "C_C") (pintype "passive"))
      (node (ref "SIM900-T2") (pin "C") (pinfunction "C_C") (pintype "passive"))
    )
    (net (code "113") (name "Net-(SIM900-R5-Pad1)") (class "Default")
      (node (ref "SIM900-R5") (pin "1") (pinfunction "1_1") (pintype "passive"))
      (node (ref "SIM900-R6") (pin "1") (pinfunction "1_1") (pintype "passive"))
      (node (ref "SIM900-T1") (pin "B") (pinfunction "B_B") (pintype "passive"))
    )
    (net (code "114") (name "Net-(SIM900-R8-Pad1)") (class "Default")
      (node (ref "SIM900-R8") (pin "1") (pinfunction "1_1") (pintype "passive"))
      (node (ref "SIM900-R9") (pin "1") (pinfunction "1_1") (pintype "passive"))
      (node (ref "SIM900-T2") (pin "B") (pinfunction "B_B") (pintype "passive"))
    )
    (net (code "115") (name "Net-(SIM900-R10-Pad2)") (class "Default")
      (node (ref "SIM900-R10") (pin "2") (pinfunction "2_2") (pintype "passive"))
      (node (ref "SIM900-T3") (pin "B") (pinfunction "B_B") (pintype "passive"))
    )
    (net (code "116") (name "Net-(STM_CHIP-PA2)") (class "Default")
      (node (ref "JP_ESP_RX") (pin "2") (pinfunction "2_2") (pintype "passive"))
      (node (ref "STM_CHIP") (pin "16") (pinfunction "PA2_16") (pintype "bidirectional"))
    )
    (net (code "117") (name "Net-(STM_CHIP-PA3)") (class "Default")
      (node (ref "JP_ESP_TX") (pin "2") (pinfunction "2_2") (pintype "passive"))
      (node (ref "STM_CHIP") (pin "17") (pinfunction "PA3_17") (pintype "bidirectional"))
    )
    (net (code "118") (name "Net-(STM_CHIP-PC14-OSC32_IN)") (class "Default")
      (node (ref "STM-C2") (pin "2") (pinfunction "2_2") (pintype "passive"))
      (node (ref "STM-XTAL") (pin "2") (pinfunction "2_2") (pintype "passive"))
      (node (ref "STM_CHIP") (pin "3") (pinfunction "PC14-OSC32_IN_3") (pintype "bidirectional"))
    )
    (net (code "119") (name "Net-(STM_CHIP-PC15-OSC32_OUT)") (class "Default")
      (node (ref "STM-C3") (pin "2") (pinfunction "2_2") (pintype "passive"))
      (node (ref "STM-XTAL") (pin "1") (pinfunction "1_1") (pintype "passive"))
      (node (ref "STM_CHIP") (pin "4") (pinfunction "PC15-OSC32_OUT_4") (pintype "bidirectional"))
    )
    (net (code "120") (name "Net-(U$4B-DCOUPL)") (class "Default")
      (node (ref "CC_DCOUP") (pin "1") (pinfunction "1_1") (pintype "passive"))
      (node (ref "U$4") (pin "27") (pinfunction "DCOUPL_27") (pintype "power_in"))
    )
    (net (code "121") (name "Net-(U$4C-RBIAS)") (class "Default")
      (node (ref "RBIAS") (pin "1") (pinfunction "1_1") (pintype "passive"))
      (node (ref "U$4") (pin "23") (pinfunction "RBIAS_23") (pintype "bidirectional"))
    )
    (net (code "122") (name "Net-(U$4C-VREG-EN)") (class "Default")
      (node (ref "R_VREG") (pin "1") (pinfunction "1_1") (pintype "passive"))
      (node (ref "U$4") (pin "26") (pinfunction "VREG-EN_26") (pintype "input"))
    )
    (net (code "123") (name "Net-(U$4C-XOSC32M-Q1)") (class "Default")
      (node (ref "CC_CX1") (pin "1") (pinfunction "1_1") (pintype "passive"))
      (node (ref "U$4") (pin "13") (pinfunction "XOSC32M-Q1_13") (pintype "input"))
      (node (ref "X1") (pin "1") (pinfunction "1_1") (pintype "bidirectional"))
    )
    (net (code "124") (name "Net-(U$4C-XOSC32M-Q2)") (class "Default")
      (node (ref "CC_CX2") (pin "1") (pinfunction "1_1") (pintype "passive"))
      (node (ref "U$4") (pin "12") (pinfunction "XOSC32M-Q2_12") (pintype "output"))
      (node (ref "X1") (pin "3") (pinfunction "2_3") (pintype "bidirectional"))
    )
    (net (code "125") (name "Net-(U$12-P$2)") (class "Default")
      (node (ref "RT2") (pin "1") (pinfunction "1_1") (pintype "passive"))
      (node (ref "U$12") (pin "PIN$2") (pinfunction "P$2_PIN$2") (pintype "bidirectional"))
    )
    (net (code "126") (name "Net-(U$12-P$3)") (class "Default")
      (node (ref "RT3") (pin "1") (pinfunction "1_1") (pintype "passive"))
      (node (ref "U$12") (pin "PIN$3") (pinfunction "P$3_PIN$3") (pintype "bidirectional"))
    )
    (net (code "127") (name "Net-(U2-1V2O)") (class "Default")
      (node (ref "U2") (pin "22") (pinfunction "1V2O_22") (pintype "passive"))
      (node (ref "W5500-C4") (pin "1") (pinfunction "1_1") (pintype "passive"))
    )
    (net (code "128") (name "Net-(U2-EXRES1)") (class "Default")
      (node (ref "U2") (pin "10") (pinfunction "EXRES1_10") (pintype "passive"))
      (node (ref "W5500-R12") (pin "2") (pinfunction "2_2") (pintype "passive"))
    )
    (net (code "129") (name "Net-(U2-RSVD-Pad23)") (class "Default")
      (node (ref "U2") (pin "23") (pinfunction "RSVD_23") (pintype "passive"))
      (node (ref "W5500-R11") (pin "2") (pinfunction "2_2") (pintype "passive"))
    )
    (net (code "130") (name "Net-(U2-TOCAP)") (class "Default")
      (node (ref "U2") (pin "20") (pinfunction "TOCAP_20") (pintype "passive"))
      (node (ref "W5500-C3") (pin "1") (pinfunction "1_1") (pintype "passive"))
    )
    (net (code "131") (name "Net-(U2-XI{slash}CLKIN)") (class "Default")
      (node (ref "U2") (pin "30") (pinfunction "XI/CLKIN_30") (pintype "passive"))
      (node (ref "W5500-C1") (pin "1") (pinfunction "1_1") (pintype "passive"))
      (node (ref "W5500-R10") (pin "1") (pinfunction "1_1") (pintype "passive"))
      (node (ref "W5500-XTAL") (pin "1") (pinfunction "1_1") (pintype "passive"))
    )
    (net (code "132") (name "Net-(U2-XO)") (class "Default")
      (node (ref "U2") (pin "31") (pinfunction "XO_31") (pintype "passive"))
      (node (ref "W5500-C2") (pin "1") (pinfunction "1_1") (pintype "passive"))
      (node (ref "W5500-R10") (pin "2") (pinfunction "2_2") (pintype "passive"))
      (node (ref "W5500-XTAL") (pin "2") (pinfunction "2_2") (pintype "passive"))
    )
    (net (code "133") (name "Q1") (class "Default")
      (node (ref "IC2") (pin "15") (pinfunction "QA_15") (pintype "tri_state"))
      (node (ref "SR_OUT1") (pin "3") (pinfunction "3_3") (pintype "passive"))
    )
    (net (code "134") (name "Q2") (class "Default")
      (node (ref "IC2") (pin "1") (pinfunction "QB_1") (pintype "tri_state"))
      (node (ref "SR_OUT1") (pin "4") (pinfunction "4_4") (pintype "passive"))
    )
    (net (code "135") (name "Q3") (class "Default")
      (node (ref "IC2") (pin "2") (pinfunction "QC_2") (pintype "tri_state"))
      (node (ref "SR_OUT1") (pin "5") (pinfunction "5_5") (pintype "passive"))
    )
    (net (code "136") (name "Q4") (class "Default")
      (node (ref "IC2") (pin "3") (pinfunction "QD_3") (pintype "tri_state"))
      (node (ref "SR_OUT1") (pin "6") (pinfunction "6_6") (pintype "passive"))
    )
    (net (code "137") (name "Q5") (class "Default")
      (node (ref "IC2") (pin "4") (pinfunction "QE_4") (pintype "tri_state"))
      (node (ref "SR_OUT1") (pin "7") (pinfunction "7_7") (pintype "passive"))
    )
    (net (code "138") (name "Q6") (class "Default")
      (node (ref "IC2") (pin "5") (pinfunction "QF_5") (pintype "tri_state"))
      (node (ref "SR_OUT1") (pin "8") (pinfunction "8_8") (pintype "passive"))
    )
    (net (code "139") (name "Q7") (class "Default")
      (node (ref "IC2") (pin "6") (pinfunction "QG_6") (pintype "tri_state"))
      (node (ref "SR_OUT1") (pin "9") (pinfunction "9_9") (pintype "passive"))
    )
    (net (code "140") (name "Q8") (class "Default")
      (node (ref "IC2") (pin "7") (pinfunction "QH_7") (pintype "tri_state"))
      (node (ref "SR_OUT1") (pin "10") (pinfunction "10_10") (pintype "passive"))
    )
    (net (code "141") (name "Q9") (class "Default")
      (node (ref "IC3") (pin "15") (pinfunction "QA_15") (pintype "tri_state"))
      (node (ref "SR_OUT2") (pin "3") (pinfunction "3_3") (pintype "passive"))
    )
    (net (code "142") (name "Q10") (class "Default")
      (node (ref "IC3") (pin "1") (pinfunction "QB_1") (pintype "tri_state"))
      (node (ref "SR_OUT2") (pin "4") (pinfunction "4_4") (pintype "passive"))
    )
    (net (code "143") (name "Q11") (class "Default")
      (node (ref "IC3") (pin "2") (pinfunction "QC_2") (pintype "tri_state"))
      (node (ref "SR_OUT2") (pin "5") (pinfunction "5_5") (pintype "passive"))
    )
    (net (code "144") (name "Q12") (class "Default")
      (node (ref "IC3") (pin "3") (pinfunction "QD_3") (pintype "tri_state"))
      (node (ref "SR_OUT2") (pin "6") (pinfunction "6_6") (pintype "passive"))
    )
    (net (code "145") (name "Q13") (class "Default")
      (node (ref "IC3") (pin "4") (pinfunction "QE_4") (pintype "tri_state"))
      (node (ref "SR_OUT2") (pin "7") (pinfunction "7_7") (pintype "passive"))
    )
    (net (code "146") (name "Q14") (class "Default")
      (node (ref "IC3") (pin "5") (pinfunction "QF_5") (pintype "tri_state"))
      (node (ref "SR_OUT2") (pin "8") (pinfunction "8_8") (pintype "passive"))
    )
    (net (code "147") (name "Q15") (class "Default")
      (node (ref "IC3") (pin "6") (pinfunction "QG_6") (pintype "tri_state"))
      (node (ref "SR_OUT2") (pin "9") (pinfunction "9_9") (pintype "passive"))
    )
    (net (code "148") (name "Q16") (class "Default")
      (node (ref "IC3") (pin "7") (pinfunction "QH_7") (pintype "tri_state"))
      (node (ref "SR_OUT2") (pin "10") (pinfunction "10_10") (pintype "passive"))
    )
    (net (code "149") (name "QS") (class "Default")
      (node (ref "IC2") (pin "9") (pinfunction "QH*_9") (pintype "tri_state"))
      (node (ref "IC3") (pin "14") (pinfunction "SER_14") (pintype "input"))
    )
    (net (code "150") (name "QS2") (class "Default")
      (node (ref "IC3") (pin "9") (pinfunction "QH*_9") (pintype "tri_state"))
      (node (ref "IC5") (pin "14") (pinfunction "SER_14") (pintype "input"))
    )
    (net (code "151") (name "R") (class "Default")
      (node (ref "RT1") (pin "1") (pinfunction "1_1") (pintype "passive"))
      (node (ref "U$12") (pin "PIN$1") (pinfunction "P$1_PIN$1") (pintype "bidirectional"))
      (node (ref "U$3") (pin "AC$1") (pinfunction "AC_IN$1_AC$1") (pintype "bidirectional"))
    )
    (net (code "152") (name "RXN") (class "Default")
      (node (ref "ETH-C4") (pin "2") (pinfunction "2_2") (pintype "passive"))
      (node (ref "ETH-R7") (pin "1") (pinfunction "1_1") (pintype "passive"))
      (node (ref "U2") (pin "5") (pinfunction "RXN_5") (pintype "passive"))
    )
    (net (code "153") (name "RXP") (class "Default")
      (node (ref "ETH-C2") (pin "2") (pinfunction "2_2") (pintype "passive"))
      (node (ref "ETH-R6") (pin "2") (pinfunction "2_2") (pintype "passive"))
      (node (ref "U2") (pin "6") (pinfunction "RXP_6") (pintype "passive"))
    )
    (net (code "154") (name "SD_CS") (class "Default")
      (node (ref "STM_CHIP") (pin "55") (pinfunction "PB3_55") (pintype "bidirectional"))
      (node (ref "U$13") (pin "SD_CS") (pinfunction "SD_CS_SD_CS") (pintype "bidirectional"))
    )
    (net (code "155") (name "SERIAL_RX") (class "Default")
      (node (ref "STM-USART") (pin "3") (pinfunction "3_3") (pintype "passive"))
      (node (ref "STM_CHIP") (pin "43") (pinfunction "PA10_43") (pintype "bidirectional"))
    )
    (net (code "156") (name "SERIAL_TX") (class "Default")
      (node (ref "STM-USART") (pin "2") (pinfunction "2_2") (pintype "passive"))
      (node (ref "STM_CHIP") (pin "42") (pinfunction "PA9_42") (pintype "bidirectional"))
    )
    (net (code "157") (name "SIM900_PWRKEY") (class "Default")
      (node (ref "IC1") (pin "P$1") (pinfunction "PWRKEY_P$1") (pintype "power_in"))
      (node (ref "SIM900-T3") (pin "C") (pinfunction "C_C") (pintype "passive"))
    )
    (net (code "158") (name "SIM_NETLIGHT") (class "Default")
      (node (ref "IC1") (pin "P$52") (pinfunction "NETLIGHT_P$52") (pintype "bidirectional"))
      (node (ref "SIM900-R8") (pin "2") (pinfunction "2_2") (pintype "passive"))
    )
    (net (code "159") (name "SIM_PWRKEY") (class "Default")
      (node (ref "SIM900-R10") (pin "1") (pinfunction "1_1") (pintype "passive"))
      (node (ref "STM_CHIP") (pin "41") (pinfunction "PA8_41") (pintype "bidirectional"))
    )
    (net (code "160") (name "SIM_RX") (class "Default")
      (node (ref "IC1") (pin "P$10") (pinfunction "RXD_P$10") (pintype "input"))
      (node (ref "STM_CHIP") (pin "51") (pinfunction "PC10_51") (pintype "bidirectional"))
    )
    (net (code "161") (name "SIM_STATUS") (class "Default")
      (node (ref "IC1") (pin "P$66") (pinfunction "STATUS_P$66") (pintype "bidirectional"))
      (node (ref "SIM900-R5") (pin "2") (pinfunction "2_2") (pintype "passive"))
    )
    (net (code "162") (name "SIM_TX") (class "Default")
      (node (ref "IC1") (pin "P$9") (pinfunction "TXD_P$9") (pintype "output"))
      (node (ref "STM_CHIP") (pin "50") (pinfunction "PA15_50") (pintype "bidirectional"))
    )
    (net (code "163") (name "SR_DS") (class "Default")
      (node (ref "IC2") (pin "14") (pinfunction "SER_14") (pintype "input"))
      (node (ref "STM_CHIP") (pin "8") (pinfunction "PC0_8") (pintype "bidirectional"))
    )
    (net (code "164") (name "SR_RST") (class "Default")
      (node (ref "IC2") (pin "10") (pinfunction "SCL_10") (pintype "input"))
      (node (ref "IC3") (pin "10") (pinfunction "SCL_10") (pintype "input"))
      (node (ref "IC5") (pin "10") (pinfunction "SCL_10") (pintype "input"))
      (node (ref "STM_CHIP") (pin "11") (pinfunction "PC3_11") (pintype "bidirectional"))
    )
    (net (code "165") (name "SR_SHCP") (class "Default")
      (node (ref "IC2") (pin "11") (pinfunction "SCK_11") (pintype "input"))
      (node (ref "IC3") (pin "11") (pinfunction "SCK_11") (pintype "input"))
      (node (ref "IC5") (pin "11") (pinfunction "SCK_11") (pintype "input"))
      (node (ref "STM_CHIP") (pin "10") (pinfunction "PC2_10") (pintype "bidirectional"))
    )
    (net (code "166") (name "SR_STCP") (class "Default")
      (node (ref "IC2") (pin "12") (pinfunction "RCK_12") (pintype "input"))
      (node (ref "IC3") (pin "12") (pinfunction "RCK_12") (pintype "input"))
      (node (ref "IC5") (pin "12") (pinfunction "RCK_12") (pintype "input"))
      (node (ref "STM_CHIP") (pin "9") (pinfunction "PC1_9") (pintype "bidirectional"))
    )
    (net (code "167") (name "SWD_NRST") (class "Default")
      (node (ref "S1") (pin "1") (pinfunction "1_1") (pintype "passive"))
      (node (ref "S1") (pin "2") (pinfunction "2_2") (pintype "passive"))
      (node (ref "STM-C8") (pin "1") (pinfunction "1_1") (pintype "passive"))
      (node (ref "STM_CHIP") (pin "7") (pinfunction "NRST_7") (pintype "bidirectional"))
    )
    (net (code "168") (name "SWD_TCK") (class "Default")
      (node (ref "STM-SWD") (pin "2") (pinfunction "2_2") (pintype "passive"))
      (node (ref "STM_CHIP") (pin "49") (pinfunction "PA14_49") (pintype "bidirectional"))
    )
    (net (code "169") (name "SWD_TMS") (class "Default")
      (node (ref "STM-SWD") (pin "4") (pinfunction "4_4") (pintype "passive"))
      (node (ref "STM_CHIP") (pin "46") (pinfunction "PA13_46") (pintype "bidirectional"))
    )
    (net (code "170") (name "TXN") (class "Default")
      (node (ref "ETH-R2") (pin "1") (pinfunction "1_1") (pintype "passive"))
      (node (ref "ETHERNET") (pin "2") (pinfunction "TX-_2") (pintype "bidirectional"))
      (node (ref "U2") (pin "1") (pinfunction "TXN_1") (pintype "passive"))
    )
    (net (code "171") (name "TXP") (class "Default")
      (node (ref "ETH-R1") (pin "1") (pinfunction "1_1") (pintype "passive"))
      (node (ref "ETHERNET") (pin "1") (pinfunction "TX+_1") (pintype "bidirectional"))
      (node (ref "U2") (pin "2") (pinfunction "TXP_2") (pintype "passive"))
    )
    (net (code "172") (name "T_CLK") (class "Default")
      (node (ref "STM_CHIP") (pin "27") (pinfunction "PB1_27") (pintype "bidirectional"))
      (node (ref "U$13") (pin "T_CLK") (pinfunction "T_CLK_T_CLK") (pintype "bidirectional"))
    )
    (net (code "173") (name "T_DIN") (class "Default")
      (node (ref "STM_CHIP") (pin "29") (pinfunction "PB10_29") (pintype "bidirectional"))
      (node (ref "U$13") (pin "T_DIN") (pinfunction "T_DIN_T_DIN") (pintype "bidirectional"))
    )
    (net (code "174") (name "T_DO") (class "Default")
      (node (ref "STM_CHIP") (pin "30") (pinfunction "PB11_30") (pintype "bidirectional"))
      (node (ref "U$13") (pin "T_DO") (pinfunction "T_DO_T_DO") (pintype "bidirectional"))
    )
    (net (code "175") (name "T_IRQ") (class "Default")
      (node (ref "STM_CHIP") (pin "28") (pinfunction "PB2_28") (pintype "bidirectional"))
      (node (ref "U$13") (pin "T_IRQ") (pinfunction "T_IRQ_T_IRQ") (pintype "bidirectional"))
    )
    (net (code "176") (name "USB_DM") (class "Default")
      (node (ref "STM_CHIP") (pin "44") (pinfunction "PA11_44") (pintype "bidirectional"))
      (node (ref "USB_IN") (pin "D-1") (pinfunction "D-_D-1") (pintype "bidirectional"))
    )
    (net (code "177") (name "USB_DP") (class "Default")
      (node (ref "STM_CHIP") (pin "45") (pinfunction "PA12_45") (pintype "bidirectional"))
      (node (ref "USB_IN") (pin "D+1") (pinfunction "D+_D+1") (pintype "bidirectional"))
    )
    (net (code "178") (name "USIM_CLK") (class "Default")
      (node (ref "SIM900-R2") (pin "2") (pinfunction "2_2") (pintype "passive"))
      (node (ref "U$8") (pin "SIM_CLK") (pinfunction "SIM_CLK_SIM_CLK") (pintype "bidirectional"))
    )
    (net (code "179") (name "USIM_DATA") (class "Default")
      (node (ref "SIM900-R3") (pin "2") (pinfunction "2_2") (pintype "passive"))
      (node (ref "U$8") (pin "SIM_IO") (pinfunction "SIM_IO_SIM_IO") (pintype "bidirectional"))
    )
    (net (code "180") (name "USIM_RESET") (class "Default")
      (node (ref "SIM900-R1") (pin "2") (pinfunction "2_2") (pintype "passive"))
      (node (ref "U$8") (pin "SIM_RST") (pinfunction "SIM_RST_SIM_RST") (pintype "bidirectional"))
    )
    (net (code "181") (name "USIM_VCC") (class "Default")
      (node (ref "IC1") (pin "P$30") (pinfunction "SIM_VDD_P$30") (pintype "power_in"))
      (node (ref "SIM900-C4") (pin "1") (pinfunction "1_1") (pintype "passive"))
      (node (ref "SIM900-C5") (pin "1") (pinfunction "1_1") (pintype "passive"))
      (node (ref "SIM_C1") (pin "2") (pinfunction "2_2") (pintype "passive"))
      (node (ref "SIM_C2") (pin "2") (pinfunction "2_2") (pintype "passive"))
      (node (ref "U$8") (pin "SIM_VDD") (pinfunction "SIM_VDD_SIM_VDD") (pintype "bidirectional"))
    )
    (net (code "182") (name "VBAT") (class "Default")
      (node (ref "BAT1") (pin "PWR@1") (pinfunction "+_PWR@1") (pintype "power_in"))
      (node (ref "STM_CHIP") (pin "1") (pinfunction "VLCD_1") (pintype "power_in"))
    )
    (net (code "183") (name "VCC") (class "Default")
      (node (ref "ETH-R1") (pin "2") (pinfunction "2_2") (pintype "passive"))
      (node (ref "ETH-R2") (pin "2") (pinfunction "2_2") (pintype "passive"))
      (node (ref "ETH-R3") (pin "2") (pinfunction "2_2") (pintype "passive"))
      (node (ref "STM-C9") (pin "1") (pinfunction "1_1") (pintype "passive"))
      (node (ref "STM-L1") (pin "2") (pinfunction "2_2") (pintype "passive"))
      (node (ref "STM_CHIP") (pin "13") (pinfunction "VDDA_13") (pintype "power_in"))
      (node (ref "SYS-C4") (pin "1") (pinfunction "1_1") (pintype "passive"))
      (node (ref "SYS-R2") (pin "2") (pinfunction "2_2") (pintype "passive"))
      (node (ref "U2") (pin "11") (pinfunction "AVDD_11") (pintype "passive"))
      (node (ref "U2") (pin "15") (pinfunction "AVDD_15") (pintype "passive"))
      (node (ref "U2") (pin "17") (pinfunction "AVDD_17") (pintype "passive"))
      (node (ref "U2") (pin "21") (pinfunction "AVDD_21") (pintype "passive"))
      (node (ref "U2") (pin "4") (pinfunction "AVDD_4") (pintype "passive"))
      (node (ref "U2") (pin "8") (pinfunction "AVDD_8") (pintype "passive"))
      (node (ref "W5500-C10") (pin "1") (pinfunction "1_1") (pintype "passive"))
      (node (ref "W5500-C11") (pin "1") (pinfunction "1_1") (pintype "passive"))
      (node (ref "W5500-C12") (pin "+") (pinfunction "+_+") (pintype "passive"))
      (node (ref "W5500-C6") (pin "1") (pinfunction "1_1") (pintype "passive"))
      (node (ref "W5500-C7") (pin "1") (pinfunction "1_1") (pintype "passive"))
      (node (ref "W5500-C8") (pin "1") (pinfunction "1_1") (pintype "passive"))
      (node (ref "W5500-C9") (pin "1") (pinfunction "1_1") (pintype "passive"))
    )
    (net (code "184") (name "VDD") (class "Default")
      (node (ref "CC_C14") (pin "1") (pinfunction "1_1") (pintype "passive"))
      (node (ref "CC_C20") (pin "1") (pinfunction "1_1") (pintype "passive"))
      (node (ref "CC_C8") (pin "1") (pinfunction "1_1") (pintype "passive"))
      (node (ref "DHT-R1") (pin "1") (pinfunction "1_1") (pintype "passive"))
      (node (ref "ESP_EXT") (pin "1") (pinfunction "1_1") (pintype "passive"))
      (node (ref "ETHERNET") (pin "12") (pinfunction "LED2_A_12") (pintype "bidirectional"))
      (node (ref "ETHERNET") (pin "9") (pinfunction "LED1_A_9") (pintype "bidirectional"))
      (node (ref "IC2") (pin "16") (pinfunction "VCC_16") (pintype "power_in"))
      (node (ref "IC3") (pin "16") (pinfunction "VCC_16") (pintype "power_in"))
      (node (ref "IC5") (pin "16") (pinfunction "VCC_16") (pintype "power_in"))
      (node (ref "LCD-R1") (pin "2") (pinfunction "2_2") (pintype "passive"))
      (node (ref "LCD_C1") (pin "1") (pinfunction "1_1") (pintype "passive"))
      (node (ref "PWR-SWT") (pin "1") (pinfunction "1_1") (pintype "passive"))
      (node (ref "RW5500-1") (pin "2") (pinfunction "1_2") (pintype "passive"))
      (node (ref "RW5500-1") (pin "3") (pinfunction "1_3") (pintype "passive"))
      (node (ref "RW5500-1") (pin "4") (pinfunction "1_4") (pintype "passive"))
      (node (ref "RW5500-3") (pin "1") (pinfunction "1_1") (pintype "passive"))
      (node (ref "R_VREG") (pin "2") (pinfunction "2_2") (pintype "passive"))
      (node (ref "SIM900-R4") (pin "2") (pinfunction "2_2") (pintype "passive"))
      (node (ref "SIM900-R7") (pin "2") (pinfunction "2_2") (pintype "passive"))
      (node (ref "STM-C1") (pin "2") (pinfunction "2_2") (pintype "passive"))
      (node (ref "STM-C10") (pin "1") (pinfunction "1_1") (pintype "passive"))
      (node (ref "STM-C11") (pin "1") (pinfunction "1_1") (pintype "passive"))
      (node (ref "STM-C12") (pin "1") (pinfunction "1_1") (pintype "passive"))
      (node (ref "STM-C13") (pin "1") (pinfunction "1_1") (pintype "passive"))
      (node (ref "STM-L1") (pin "1") (pinfunction "1_1") (pintype "passive"))
      (node (ref "STM-SWD") (pin "1") (pinfunction "1_1") (pintype "passive"))
      (node (ref "STM-USART") (pin "1") (pinfunction "1_1") (pintype "passive"))
      (node (ref "STM_CHIP") (pin "19") (pinfunction "VDD_4_19") (pintype "power_in"))
      (node (ref "STM_CHIP") (pin "32") (pinfunction "VDD_1_32") (pintype "power_in"))
      (node (ref "STM_CHIP") (pin "48") (pinfunction "VDD_2_48") (pintype "power_in"))
      (node (ref "STM_CHIP") (pin "64") (pinfunction "VDD_3_64") (pintype "power_in"))
      (node (ref "SYS-C3") (pin "1") (pinfunction "1_1") (pintype "passive"))
      (node (ref "SYS-L2") (pin "2") (pinfunction "2_2") (pintype "passive"))
      (node (ref "SYS-R2") (pin "1") (pinfunction "1_1") (pintype "passive"))
      (node (ref "U$13") (pin "LCD_VCC") (pinfunction "LCD_VCC_LCD_VCC") (pintype "power_in"))
      (node (ref "U$17") (pin "VCC") (pinfunction "VCC_VCC") (pintype "bidirectional"))
      (node (ref "U$4") (pin "11") (pinfunction "AVDD_11") (pintype "power_in"))
      (node (ref "U$4") (pin "14") (pinfunction "AVDD_14") (pintype "power_in"))
      (node (ref "U$4") (pin "16") (pinfunction "AVDD_16") (pintype "power_in"))
      (node (ref "U$4") (pin "20") (pinfunction "AVDD_20") (pintype "power_in"))
      (node (ref "U$4") (pin "22") (pinfunction "AVDD_22") (pintype "power_in"))
      (node (ref "U$4") (pin "24") (pinfunction "AVDD-GUARD_24") (pintype "power_in"))
      (node (ref "U$4") (pin "8") (pinfunction "DVDD_8") (pintype "power_in"))
      (node (ref "U2") (pin "28") (pinfunction "VDD_28") (pintype "passive"))
      (node (ref "W5500-C13") (pin "+") (pinfunction "+_+") (pintype "passive"))
      (node (ref "W5500-C5") (pin "1") (pinfunction "1_1") (pintype "passive"))
      (node (ref "W5500-R13") (pin "2") (pinfunction "2_2") (pintype "passive"))
    )
    (net (code "185") (name "VESP") (class "Default")
      (node (ref "ESP-C1") (pin "1") (pinfunction "1_1") (pintype "passive"))
      (node (ref "ESP-GPIO0") (pin "1") (pinfunction "1_1") (pintype "passive"))
      (node (ref "ESP_EXT") (pin "2") (pinfunction "2_2") (pintype "passive"))
      (node (ref "U$5") (pin "CH_PD") (pinfunction "CH_PD_CH_PD") (pintype "bidirectional"))
      (node (ref "U$5") (pin "GPIO02") (pinfunction "GPIO2_GPIO02") (pintype "bidirectional"))
      (node (ref "U$5") (pin "REST") (pinfunction "REST_REST") (pintype "bidirectional"))
      (node (ref "U$5") (pin "VCC") (pinfunction "VCC_VCC") (pintype "power_in"))
    )
    (net (code "186") (name "unconnected-(IC1-ADC-PadP$25)") (class "Default")
      (node (ref "IC1") (pin "P$25") (pinfunction "ADC_P$25") (pintype "bidirectional"))
    )
    (net (code "187") (name "unconnected-(IC1-CTS-PadP$7)") (class "Default")
      (node (ref "IC1") (pin "P$7") (pinfunction "CTS_P$7") (pintype "output"))
    )
    (net (code "188") (name "unconnected-(IC1-DBG_RXD-PadP$28)") (class "Default")
      (node (ref "IC1") (pin "P$28") (pinfunction "DBG_RXD_P$28") (pintype "input"))
    )
    (net (code "189") (name "unconnected-(IC1-DBG_TXD-PadP$27)") (class "Default")
      (node (ref "IC1") (pin "P$27") (pinfunction "DBG_TXD_P$27") (pintype "output"))
    )
    (net (code "190") (name "unconnected-(IC1-DCD-PadP$5)") (class "Default")
      (node (ref "IC1") (pin "P$5") (pinfunction "DCD_P$5") (pintype "output"))
    )
    (net (code "191") (name "unconnected-(IC1-DISP_CLK-PadP$11)") (class "Default")
      (node (ref "IC1") (pin "P$11") (pinfunction "DISP_CLK_P$11") (pintype "bidirectional"))
    )
    (net (code "192") (name "unconnected-(IC1-DISP_CS-PadP$14)") (class "Default")
      (node (ref "IC1") (pin "P$14") (pinfunction "DISP_CS_P$14") (pintype "bidirectional"))
    )
    (net (code "193") (name "unconnected-(IC1-DISP_DATA-PadP$12)") (class "Default")
      (node (ref "IC1") (pin "P$12") (pinfunction "DISP_DATA_P$12") (pintype "bidirectional"))
    )
    (net (code "194") (name "unconnected-(IC1-DISP_DC-PadP$13)") (class "Default")
      (node (ref "IC1") (pin "P$13") (pinfunction "DISP_DC_P$13") (pintype "bidirectional"))
    )
    (net (code "195") (name "unconnected-(IC1-DTR-PadP$3)") (class "Default")
      (node (ref "IC1") (pin "P$3") (pinfunction "DTR_P$3") (pintype "input"))
    )
    (net (code "196") (name "unconnected-(IC1-GPIO1{slash}KBR4-PadP$40)") (class "Default")
      (node (ref "IC1") (pin "P$40") (pinfunction "GPIO1/KBR4_P$40") (pintype "bidirectional"))
    )
    (net (code "197") (name "unconnected-(IC1-GPIO2{slash}KBR3-PadP$41)") (class "Default")
      (node (ref "IC1") (pin "P$41") (pinfunction "GPIO2/KBR3_P$41") (pintype "bidirectional"))
    )
    (net (code "198") (name "unconnected-(IC1-GPIO3{slash}KBR2-PadP$42)") (class "Default")
      (node (ref "IC1") (pin "P$42") (pinfunction "GPIO3/KBR2_P$42") (pintype "bidirectional"))
    )
    (net (code "199") (name "unconnected-(IC1-GPIO4{slash}KBR1-PadP$43)") (class "Default")
      (node (ref "IC1") (pin "P$43") (pinfunction "GPIO4/KBR1_P$43") (pintype "bidirectional"))
    )
    (net (code "200") (name "unconnected-(IC1-GPIO5{slash}KBR0-PadP$44)") (class "Default")
      (node (ref "IC1") (pin "P$44") (pinfunction "GPIO5/KBR0_P$44") (pintype "bidirectional"))
    )
    (net (code "201") (name "unconnected-(IC1-GPIO6{slash}KBC4-PadP$47)") (class "Default")
      (node (ref "IC1") (pin "P$47") (pinfunction "GPIO6/KBC4_P$47") (pintype "bidirectional"))
    )
    (net (code "202") (name "unconnected-(IC1-GPIO7{slash}KBC3-PadP$48)") (class "Default")
      (node (ref "IC1") (pin "P$48") (pinfunction "GPIO7/KBC3_P$48") (pintype "bidirectional"))
    )
    (net (code "203") (name "unconnected-(IC1-GPIO8{slash}KBC2-PadP$49)") (class "Default")
      (node (ref "IC1") (pin "P$49") (pinfunction "GPIO8/KBC2_P$49") (pintype "bidirectional"))
    )
    (net (code "204") (name "unconnected-(IC1-GPIO9{slash}KBC1-PadP$50)") (class "Default")
      (node (ref "IC1") (pin "P$50") (pinfunction "GPIO9/KBC1_P$50") (pintype "bidirectional"))
    )
    (net (code "205") (name "unconnected-(IC1-GPIO10-PadP$51)") (class "Default")
      (node (ref "IC1") (pin "P$51") (pinfunction "GPIO10_P$51") (pintype "bidirectional"))
    )
    (net (code "206") (name "unconnected-(IC1-LINEIN_L-PadP$24)") (class "Default")
      (node (ref "IC1") (pin "P$24") (pinfunction "LINEIN_L_P$24") (pintype "bidirectional"))
    )
    (net (code "207") (name "unconnected-(IC1-LINEIN_R-PadP$23)") (class "Default")
      (node (ref "IC1") (pin "P$23") (pinfunction "LINEIN_R_P$23") (pintype "bidirectional"))
    )
    (net (code "208") (name "unconnected-(IC1-MIC_N-PadP$20)") (class "Default")
      (node (ref "IC1") (pin "P$20") (pinfunction "MIC_N_P$20") (pintype "bidirectional"))
    )
    (net (code "209") (name "unconnected-(IC1-MIC_P-PadP$19)") (class "Default")
      (node (ref "IC1") (pin "P$19") (pinfunction "MIC_P_P$19") (pintype "bidirectional"))
    )
    (net (code "210") (name "unconnected-(IC1-NC-PadP$2)") (class "Default")
      (node (ref "IC1") (pin "P$2") (pinfunction "NC_P$2") (pintype "no_connect"))
    )
    (net (code "211") (name "unconnected-(IC1-NC-PadP$6)") (class "Default")
      (node (ref "IC1") (pin "P$6") (pinfunction "NC_P$6") (pintype "no_connect"))
    )
    (net (code "212") (name "unconnected-(IC1-NRESET-PadP$16)") (class "Default")
      (node (ref "IC1") (pin "P$16") (pinfunction "NRESET_P$16") (pintype "bidirectional"))
    )
    (net (code "213") (name "unconnected-(IC1-PWM1-PadP$35)") (class "Default")
      (node (ref "IC1") (pin "P$35") (pinfunction "PWM1_P$35") (pintype "bidirectional"))
    )
    (net (code "214") (name "unconnected-(IC1-PWM2-PadP$36)") (class "Default")
      (node (ref "IC1") (pin "P$36") (pinfunction "PWM2_P$36") (pintype "bidirectional"))
    )
    (net (code "215") (name "unconnected-(IC1-RI-PadP$4)") (class "Default")
      (node (ref "IC1") (pin "P$4") (pinfunction "RI_P$4") (pintype "output"))
    )
    (net (code "216") (name "unconnected-(IC1-RTS-PadP$8)") (class "Default")
      (node (ref "IC1") (pin "P$8") (pinfunction "RTS_P$8") (pintype "input"))
    )
    (net (code "217") (name "unconnected-(IC1-SCL-PadP$38)") (class "Default")
      (node (ref "IC1") (pin "P$38") (pinfunction "SCL_P$38") (pintype "bidirectional"))
    )
    (net (code "218") (name "unconnected-(IC1-SDA-PadP$37)") (class "Default")
      (node (ref "IC1") (pin "P$37") (pinfunction "SDA_P$37") (pintype "bidirectional"))
    )
    (net (code "219") (name "unconnected-(IC1-SIM_PRESENCE-PadP$34)") (class "Default")
      (node (ref "IC1") (pin "P$34") (pinfunction "SIM_PRESENCE_P$34") (pintype "bidirectional"))
    )
    (net (code "220") (name "unconnected-(IC1-SPK_N-PadP$22)") (class "Default")
      (node (ref "IC1") (pin "P$22") (pinfunction "SPK_N_P$22") (pintype "bidirectional"))
    )
    (net (code "221") (name "unconnected-(IC1-SPK_P-PadP$21)") (class "Default")
      (node (ref "IC1") (pin "P$21") (pinfunction "SPK_P_P$21") (pintype "bidirectional"))
    )
    (net (code "222") (name "unconnected-(IC1-VDD_EXT-PadP$15)") (class "Default")
      (node (ref "IC1") (pin "P$15") (pinfunction "VDD_EXT_P$15") (pintype "bidirectional"))
    )
    (net (code "223") (name "unconnected-(IC5A-QE-Pad4)") (class "Default")
      (node (ref "IC5") (pin "4") (pinfunction "QE_4") (pintype "tri_state"))
    )
    (net (code "224") (name "unconnected-(IC5A-QF-Pad5)") (class "Default")
      (node (ref "IC5") (pin "5") (pinfunction "QF_5") (pintype "tri_state"))
    )
    (net (code "225") (name "unconnected-(IC5A-QG-Pad6)") (class "Default")
      (node (ref "IC5") (pin "6") (pinfunction "QG_6") (pintype "tri_state"))
    )
    (net (code "226") (name "unconnected-(IC5A-QH*-Pad9)") (class "Default")
      (node (ref "IC5") (pin "9") (pinfunction "QH*_9") (pintype "tri_state"))
    )
    (net (code "227") (name "unconnected-(IC5A-QH-Pad7)") (class "Default")
      (node (ref "IC5") (pin "7") (pinfunction "QH_7") (pintype "tri_state"))
    )
    (net (code "228") (name "unconnected-(STM_CHIP-BOOT0-Pad60)") (class "Default")
      (node (ref "STM_CHIP") (pin "60") (pinfunction "BOOT0_60") (pintype "input"))
    )
    (net (code "229") (name "unconnected-(STM_CHIP-PH0_-OSC_IN-Pad5)") (class "Default")
      (node (ref "STM_CHIP") (pin "5") (pinfunction "PH0_-OSC_IN_5") (pintype "bidirectional"))
    )
    (net (code "230") (name "unconnected-(U$5-GPIO4-PadGPIO04)") (class "Default")
      (node (ref "U$5") (pin "GPIO04") (pinfunction "GPIO4_GPIO04") (pintype "bidirectional"))
    )
    (net (code "231") (name "unconnected-(U$5-GPIO5-PadGPIO05)") (class "Default")
      (node (ref "U$5") (pin "GPIO05") (pinfunction "GPIO5_GPIO05") (pintype "bidirectional"))
    )
    (net (code "232") (name "unconnected-(U$5-PadADC)") (class "Default")
      (node (ref "U$5") (pin "ADC") (pinfunction "ADC_ADC") (pintype "bidirectional"))
    )
    (net (code "233") (name "unconnected-(U$5-PadGPIO12)") (class "Default")
      (node (ref "U$5") (pin "GPIO12") (pinfunction "GPIO12_GPIO12") (pintype "bidirectional"))
    )
    (net (code "234") (name "unconnected-(U$5-PadGPIO13)") (class "Default")
      (node (ref "U$5") (pin "GPIO13") (pinfunction "GPIO13_GPIO13") (pintype "bidirectional"))
    )
    (net (code "235") (name "unconnected-(U$5-PadGPIO14)") (class "Default")
      (node (ref "U$5") (pin "GPIO14") (pinfunction "GPIO14_GPIO14") (pintype "bidirectional"))
    )
    (net (code "236") (name "unconnected-(U$5-PadGPIO16)") (class "Default")
      (node (ref "U$5") (pin "GPIO16") (pinfunction "GPIO16_GPIO16") (pintype "bidirectional"))
    )
    (net (code "237") (name "unconnected-(U$8-PadVPP)") (class "Default")
      (node (ref "U$8") (pin "VPP") (pinfunction "VPP_VPP") (pintype "bidirectional"))
    )
    (net (code "238") (name "unconnected-(U$17-PadNO)") (class "Default")
      (node (ref "U$17") (pin "NO") (pinfunction "NO_NO") (pintype "bidirectional"))
    )
    (net (code "239") (name "unconnected-(U2-DNC-Pad7)") (class "Default")
      (node (ref "U2") (pin "7") (pinfunction "DNC_7") (pintype "passive"))
    )
    (net (code "240") (name "unconnected-(U2-DUPLED-Pad26)") (class "Default")
      (node (ref "U2") (pin "26") (pinfunction "DUPLED_26") (pintype "passive"))
    )
    (net (code "241") (name "unconnected-(U2-INT_N-Pad36)") (class "Default")
      (node (ref "U2") (pin "36") (pinfunction "INT_N_36") (pintype "passive"))
    )
    (net (code "242") (name "unconnected-(U2-NC-Pad12)") (class "Default")
      (node (ref "U2") (pin "12") (pinfunction "NC_12") (pintype "passive"))
    )
    (net (code "243") (name "unconnected-(U2-NC-Pad13)") (class "Default")
      (node (ref "U2") (pin "13") (pinfunction "NC_13") (pintype "passive"))
    )
    (net (code "244") (name "unconnected-(U2-NC-Pad46)") (class "Default")
      (node (ref "U2") (pin "46") (pinfunction "NC_46") (pintype "passive"))
    )
    (net (code "245") (name "unconnected-(U2-NC-Pad47)") (class "Default")
      (node (ref "U2") (pin "47") (pinfunction "NC_47") (pintype "passive"))
    )
    (net (code "246") (name "unconnected-(U2-SPDLED-Pad24)") (class "Default")
      (node (ref "U2") (pin "24") (pinfunction "SPDLED_24") (pintype "passive"))
    )
    (net (code "247") (name "unconnected-(U2-VBG-Pad18)") (class "Default")
      (node (ref "U2") (pin "18") (pinfunction "VBG_18") (pintype "passive"))
    )
    (net (code "248") (name "unconnected-(USB_IN-ID-PadID1)") (class "Default")
      (node (ref "USB_IN") (pin "ID1") (pinfunction "ID_ID1") (pintype "bidirectional"))
    )
  )
)
